# module.net
KiCad netlist of a schematic drawn in EAGLE
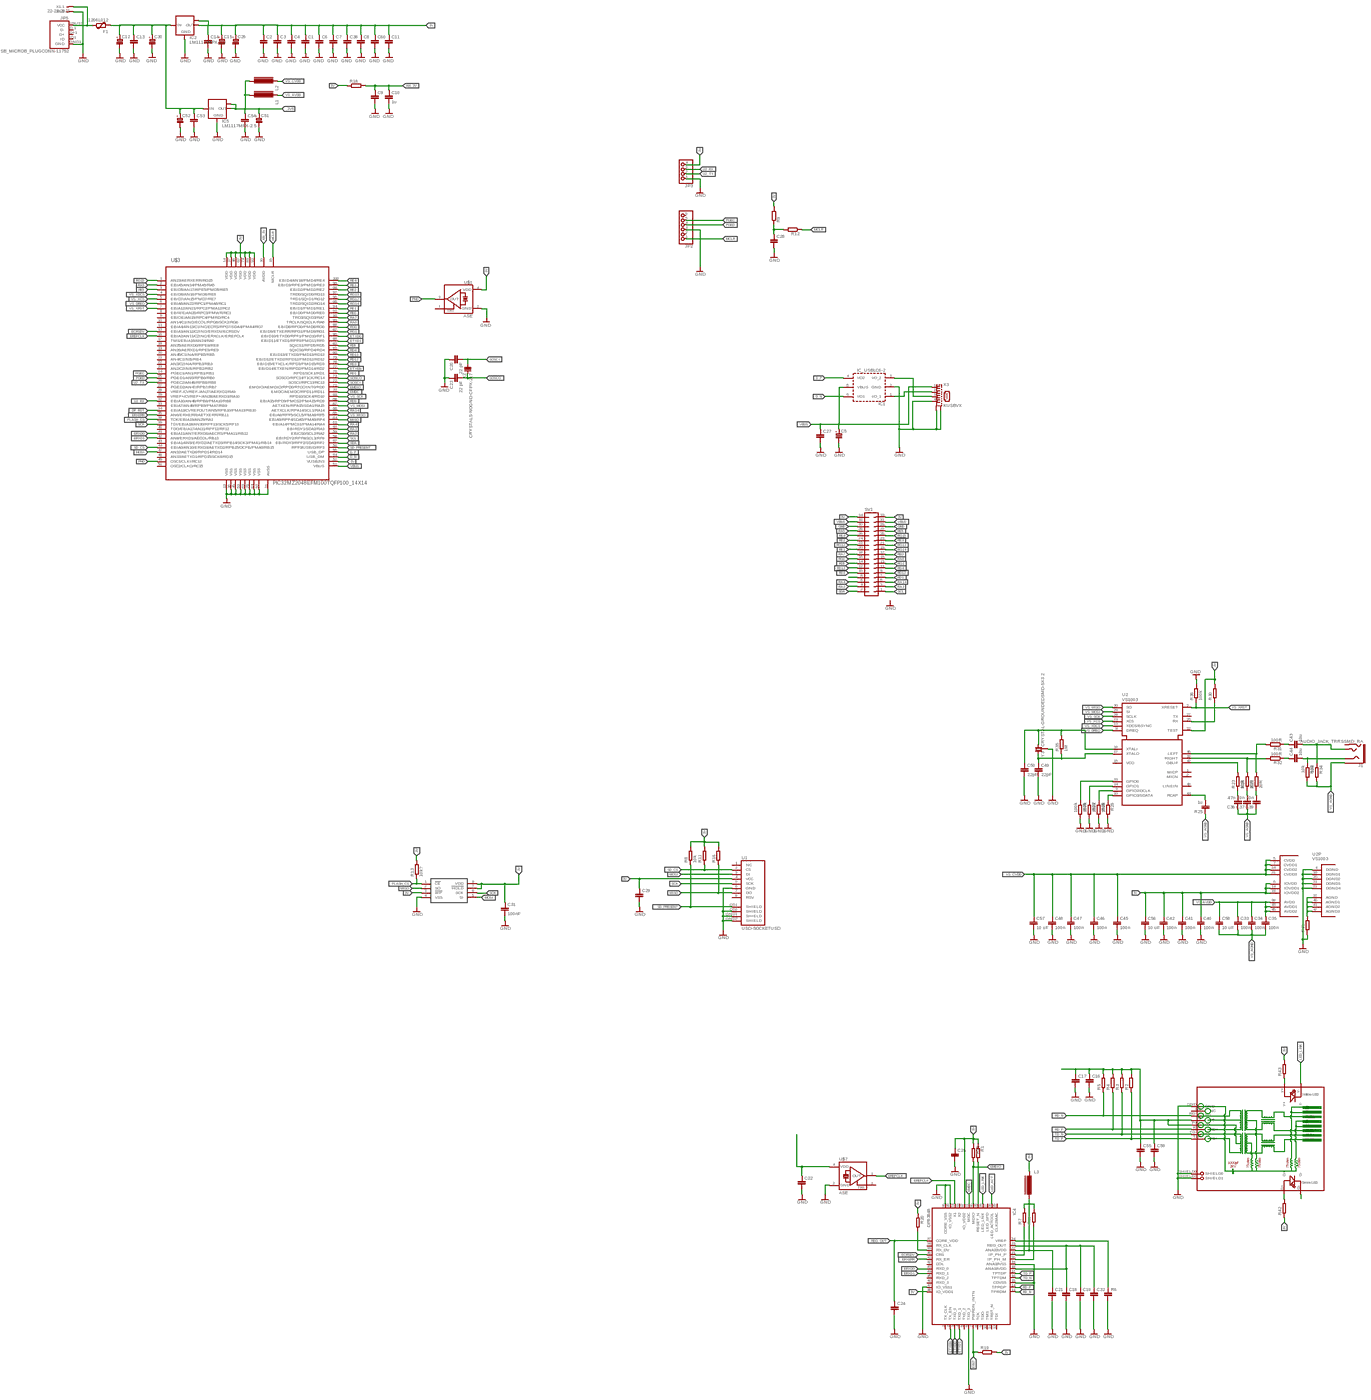
[diagram p0: schematic, sheet 1, overview]
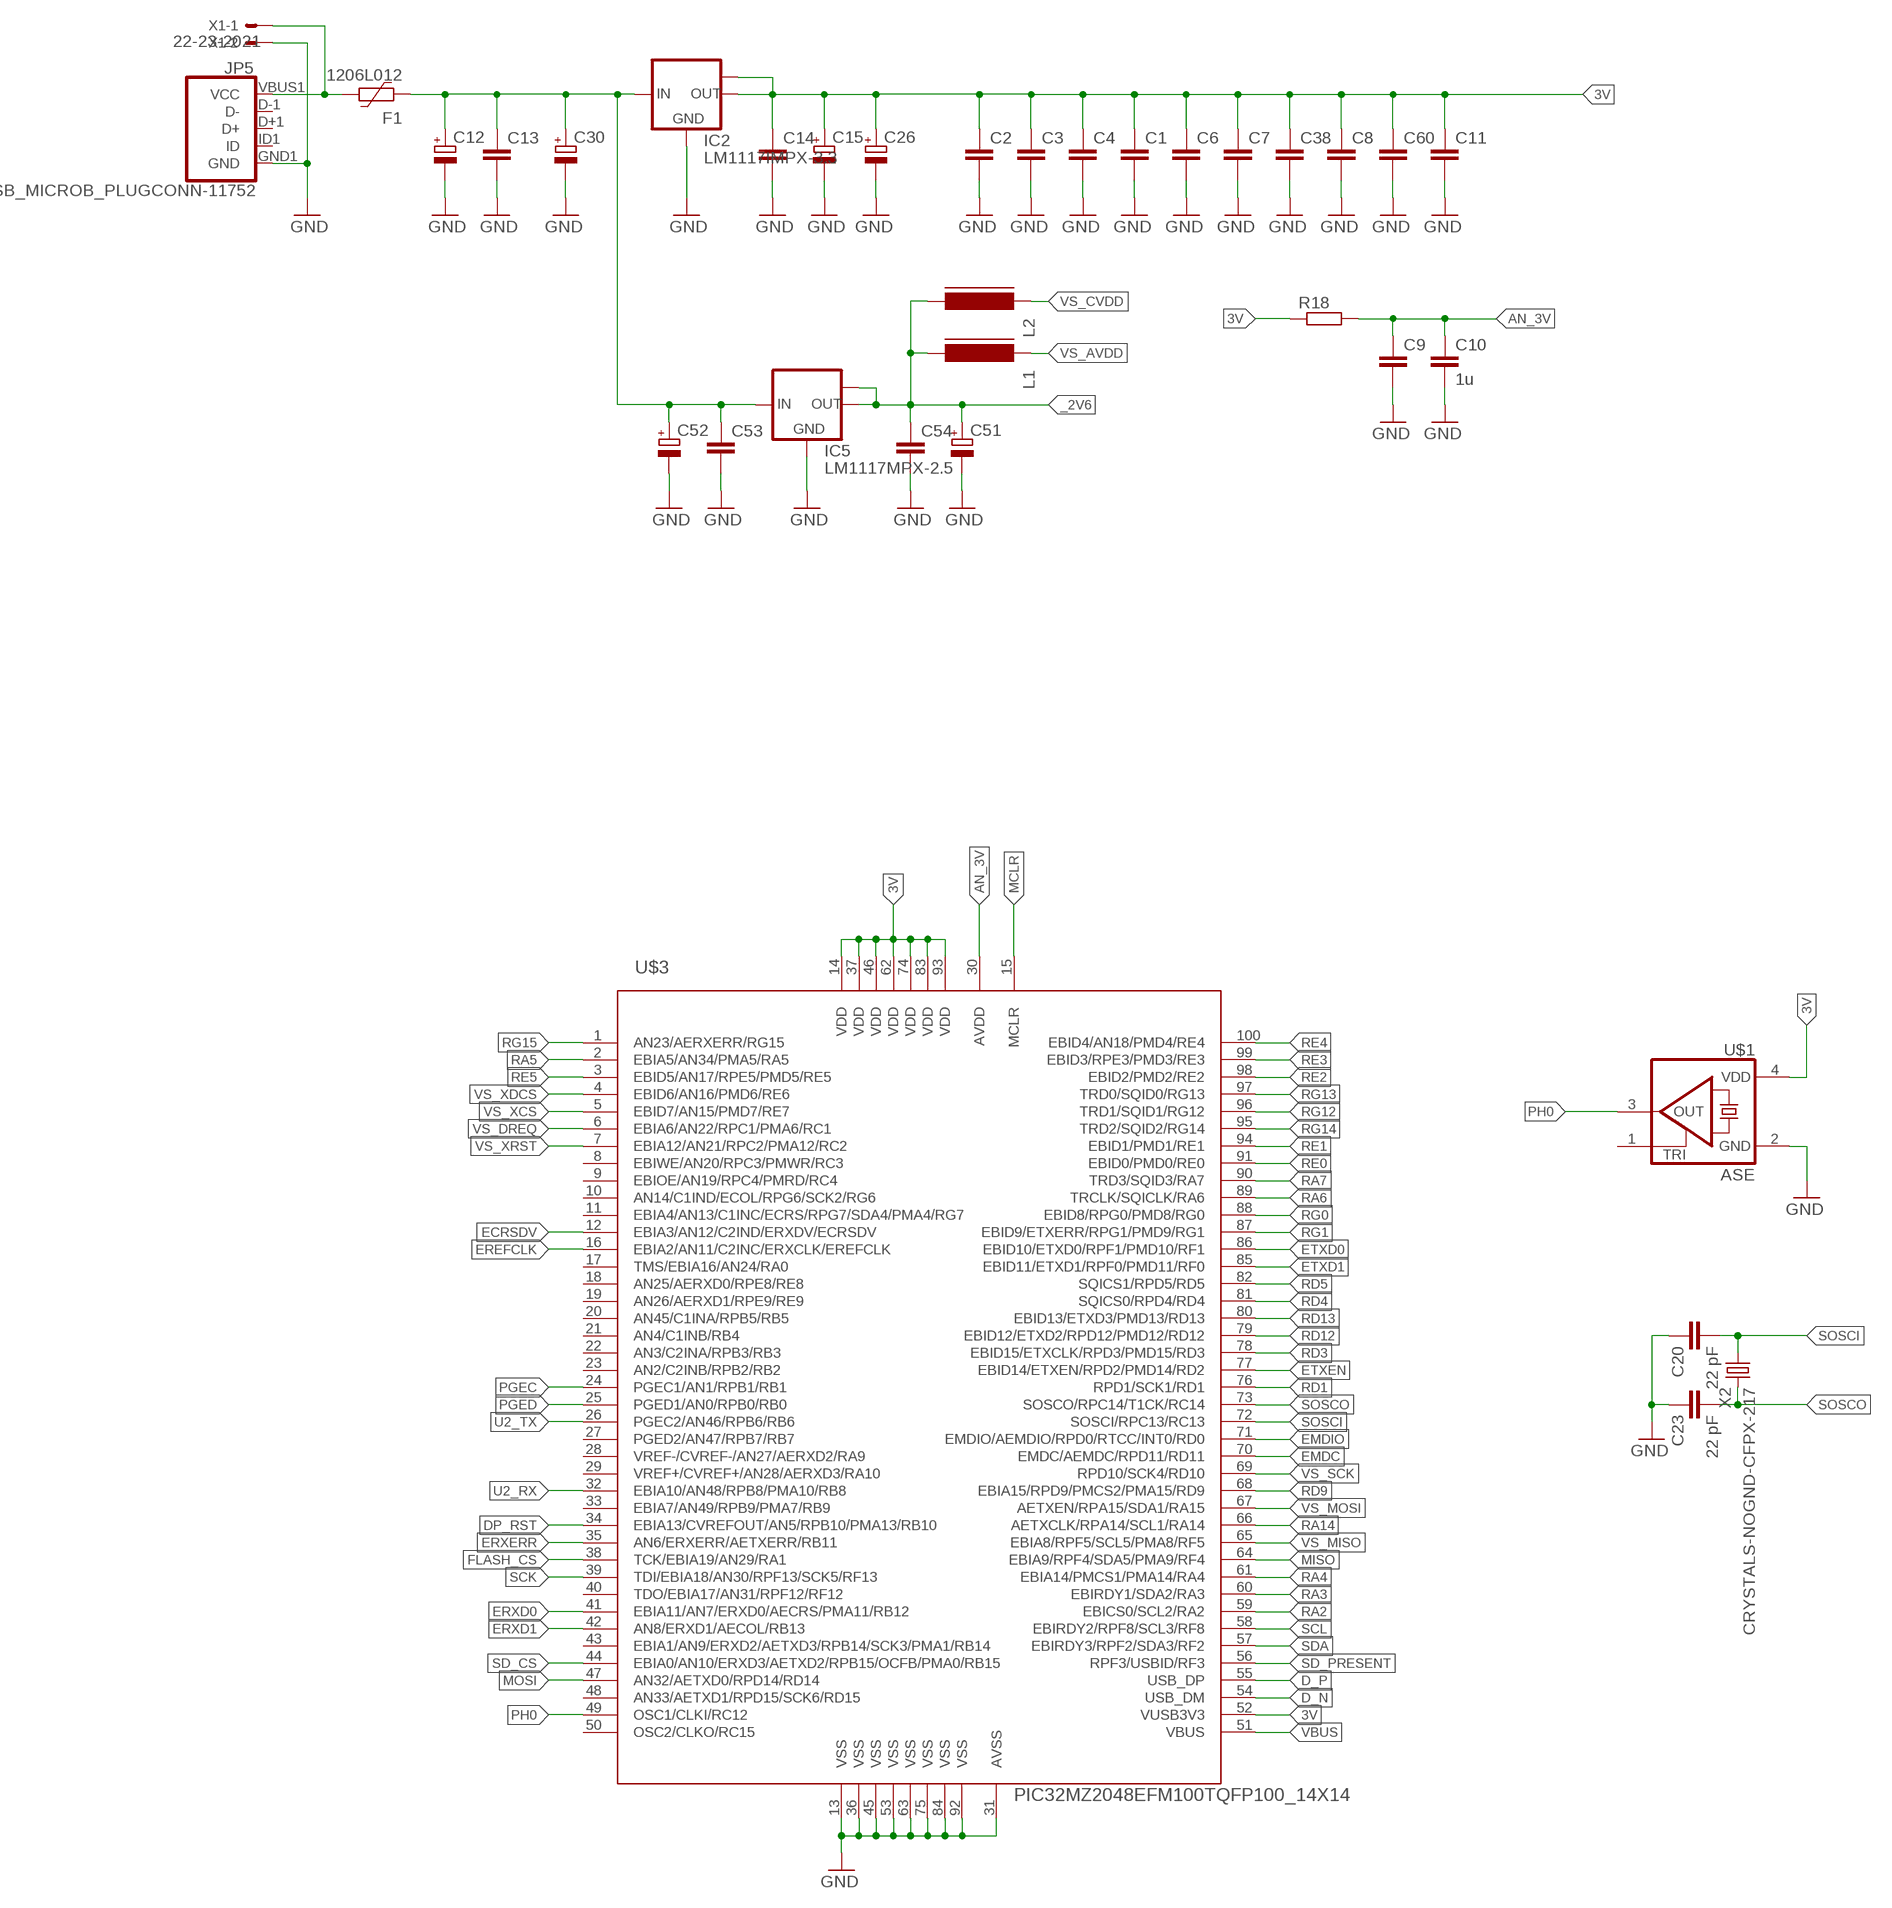
[diagram p1: schematic, sheet 1, part 1 of 4]
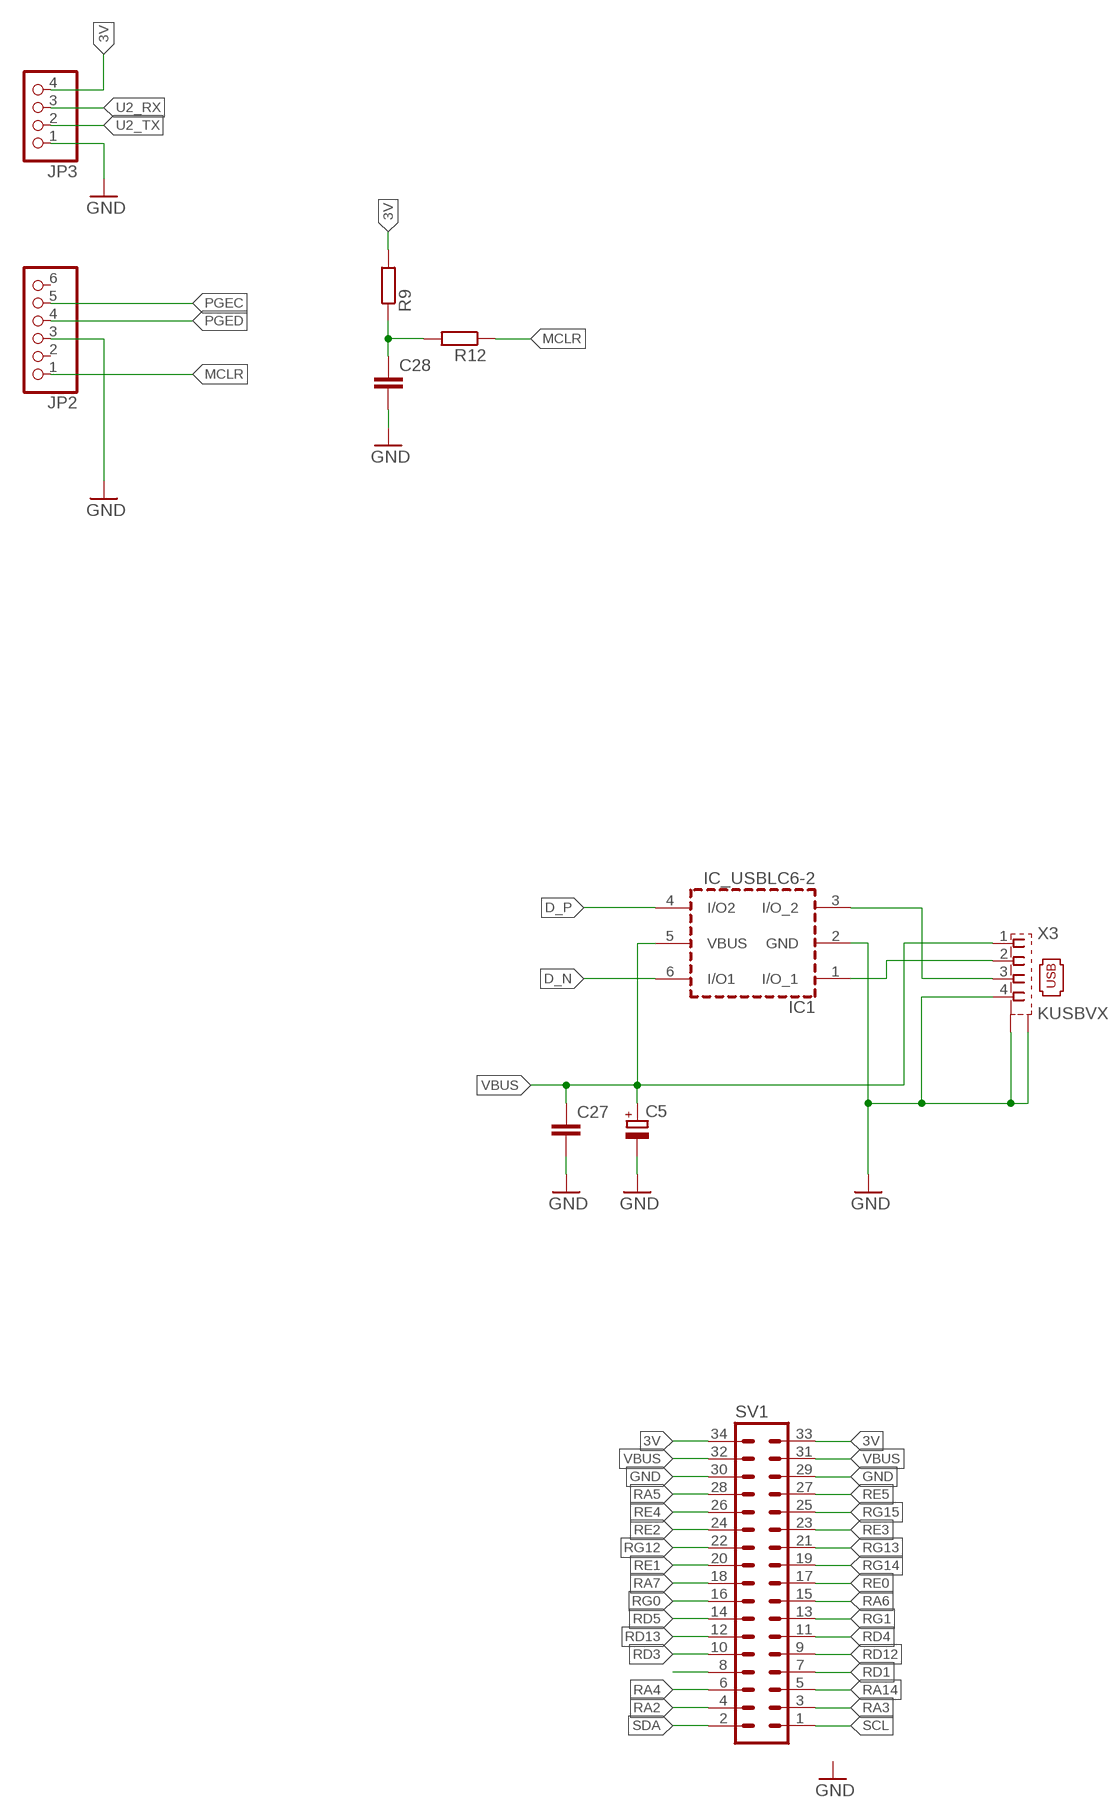
[diagram p2: schematic, sheet 1, part 2 of 4]
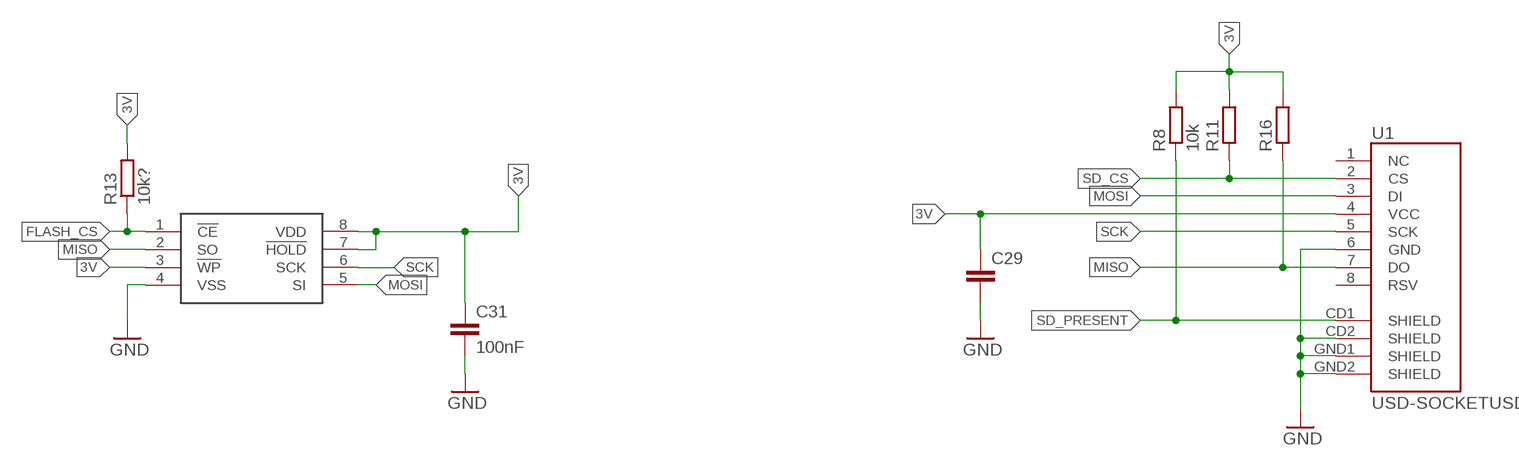
[diagram p3: schematic, sheet 1, part 3 of 4]
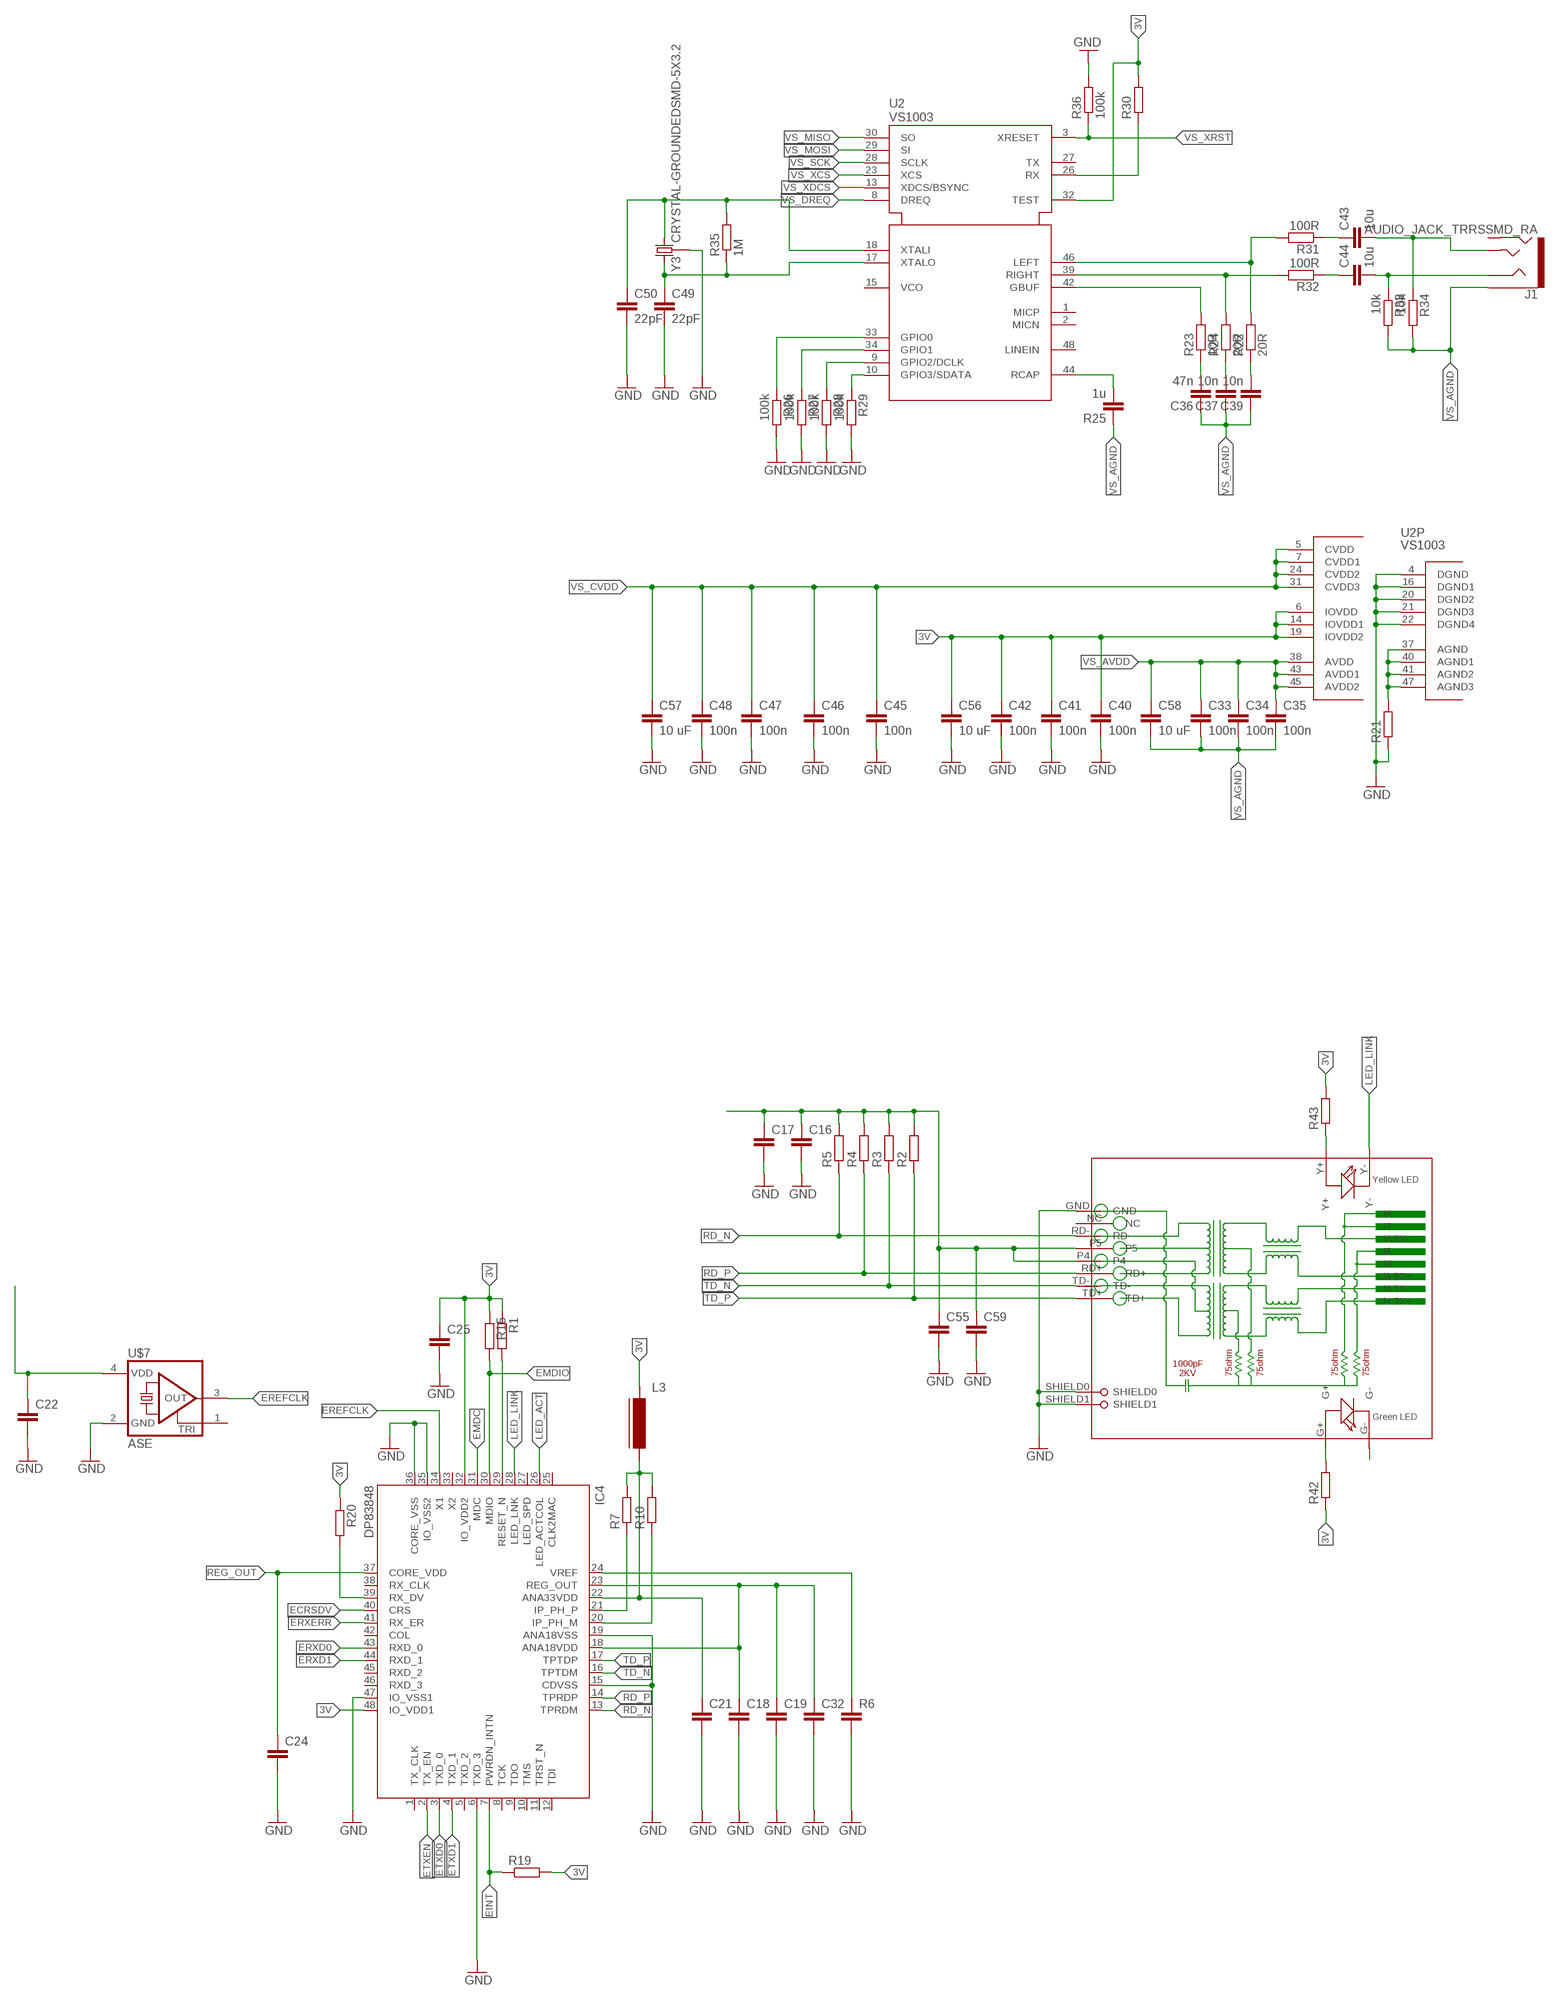
[diagram p4: schematic, sheet 1, part 4 of 4]

(export (version "E")
  (design (tool "Eeschema 10.0.6"))
  (components
    (comp (ref "C1")
      (value "C-EUC0402")
      (footprint "eagle-import:C0402")
      (libsource (lib "eagle-import") (part "C-EUC0402"))
    )
    (comp (ref "C2")
      (value "C-EUC0402")
      (footprint "eagle-import:C0402")
      (libsource (lib "eagle-import") (part "C-EUC0402"))
    )
    (comp (ref "C3")
      (value "C-EUC0402")
      (footprint "eagle-import:C0402")
      (libsource (lib "eagle-import") (part "C-EUC0402"))
    )
    (comp (ref "C4")
      (value "C-EUC0402")
      (footprint "eagle-import:C0402")
      (libsource (lib "eagle-import") (part "C-EUC0402"))
    )
    (comp (ref "C5")
      (value "CPOL-EUSMCA")
      (footprint "eagle-import:SMC_A")
      (libsource (lib "eagle-import") (part "CPOL-EUSMCA"))
    )
    (comp (ref "C6")
      (value "C-EUC0402")
      (footprint "eagle-import:C0402")
      (libsource (lib "eagle-import") (part "C-EUC0402"))
    )
    (comp (ref "C7")
      (value "C-EUC0402")
      (footprint "eagle-import:C0402")
      (libsource (lib "eagle-import") (part "C-EUC0402"))
    )
    (comp (ref "C8")
      (value "C-EUC0402")
      (footprint "eagle-import:C0402")
      (libsource (lib "eagle-import") (part "C-EUC0402"))
    )
    (comp (ref "C9")
      (value "C-EUC0402")
      (footprint "eagle-import:C0402")
      (libsource (lib "eagle-import") (part "C-EUC0402"))
    )
    (comp (ref "C10")
      (value "1u")
      (footprint "eagle-import:C0603")
      (libsource (lib "eagle-import") (part "C-EUC0603"))
    )
    (comp (ref "C11")
      (value "C-EUC0402")
      (footprint "eagle-import:C0402")
      (libsource (lib "eagle-import") (part "C-EUC0402"))
    )
    (comp (ref "C12")
      (value "CPOL-EUSMCB")
      (footprint "eagle-import:SMC_B")
      (libsource (lib "eagle-import") (part "CPOL-EUSMCB"))
    )
    (comp (ref "C13")
      (value "C-EUC0603")
      (footprint "eagle-import:C0603")
      (libsource (lib "eagle-import") (part "C-EUC0603"))
    )
    (comp (ref "C14")
      (value "C-EUC0603")
      (footprint "eagle-import:C0603")
      (libsource (lib "eagle-import") (part "C-EUC0603"))
    )
    (comp (ref "C15")
      (value "CPOL-EUSMCB")
      (footprint "eagle-import:SMC_B")
      (libsource (lib "eagle-import") (part "CPOL-EUSMCB"))
    )
    (comp (ref "C16")
      (value "C-EUC0603")
      (footprint "eagle-import:C0603")
      (libsource (lib "eagle-import") (part "C-EUC0603"))
    )
    (comp (ref "C17")
      (value "C-EUC0603")
      (footprint "eagle-import:C0603")
      (libsource (lib "eagle-import") (part "C-EUC0603"))
    )
    (comp (ref "C18")
      (value "C-EUC0402")
      (footprint "eagle-import:C0402")
      (libsource (lib "eagle-import") (part "C-EUC0402"))
    )
    (comp (ref "C19")
      (value "C-EUC0402")
      (footprint "eagle-import:C0402")
      (libsource (lib "eagle-import") (part "C-EUC0402"))
    )
    (comp (ref "C20")
      (value "22 pF")
      (footprint "eagle-import:C0603")
      (libsource (lib "eagle-import") (part "C-EUC0603"))
    )
    (comp (ref "C21")
      (value "C-EUC0402")
      (footprint "eagle-import:C0402")
      (libsource (lib "eagle-import") (part "C-EUC0402"))
    )
    (comp (ref "C22")
      (value "C-EUC0402")
      (footprint "eagle-import:C0402")
      (libsource (lib "eagle-import") (part "C-EUC0402"))
    )
    (comp (ref "C23")
      (value "22 pF")
      (footprint "eagle-import:C0603")
      (libsource (lib "eagle-import") (part "C-EUC0603"))
    )
    (comp (ref "C24")
      (value "C-EUC0603")
      (footprint "eagle-import:C0603")
      (libsource (lib "eagle-import") (part "C-EUC0603"))
    )
    (comp (ref "C25")
      (value "C-EUC0603")
      (footprint "eagle-import:C0603")
      (libsource (lib "eagle-import") (part "C-EUC0603"))
    )
    (comp (ref "C26")
      (value "CPOL-EUSMCA")
      (footprint "eagle-import:SMC_A")
      (libsource (lib "eagle-import") (part "CPOL-EUSMCA"))
    )
    (comp (ref "C27")
      (value "C-EUC0603")
      (footprint "eagle-import:C0603")
      (libsource (lib "eagle-import") (part "C-EUC0603"))
    )
    (comp (ref "C28")
      (value "C-EUC0603")
      (footprint "eagle-import:C0603")
      (libsource (lib "eagle-import") (part "C-EUC0603"))
    )
    (comp (ref "C29")
      (value "C-EUC0603")
      (footprint "eagle-import:C0603")
      (libsource (lib "eagle-import") (part "C-EUC0603"))
    )
    (comp (ref "C30")
      (value "CPOL-EUSMCA")
      (footprint "eagle-import:SMC_A")
      (libsource (lib "eagle-import") (part "CPOL-EUSMCA"))
    )
    (comp (ref "C31")
      (value "100nF")
      (footprint "eagle-import:C0603")
      (libsource (lib "eagle-import") (part "C-EUC0603"))
    )
    (comp (ref "C32")
      (value "C-EUC0603")
      (footprint "eagle-import:C0603")
      (libsource (lib "eagle-import") (part "C-EUC0603"))
    )
    (comp (ref "C33")
      (value "100n")
      (footprint "eagle-import:C0603")
      (libsource (lib "eagle-import") (part "C-EUC0603"))
    )
    (comp (ref "C34")
      (value "100n")
      (footprint "eagle-import:C0603")
      (libsource (lib "eagle-import") (part "C-EUC0603"))
    )
    (comp (ref "C35")
      (value "100n")
      (footprint "eagle-import:C0603")
      (libsource (lib "eagle-import") (part "C-EUC0603"))
    )
    (comp (ref "C36")
      (value "47n")
      (footprint "eagle-import:C0603")
      (libsource (lib "eagle-import") (part "C-EUC0603"))
    )
    (comp (ref "C37")
      (value "10n")
      (footprint "eagle-import:C0603")
      (libsource (lib "eagle-import") (part "C-EUC0603"))
    )
    (comp (ref "C38")
      (value "C-EUC0402")
      (footprint "eagle-import:C0402")
      (libsource (lib "eagle-import") (part "C-EUC0402"))
    )
    (comp (ref "C39")
      (value "10n")
      (footprint "eagle-import:C0603")
      (libsource (lib "eagle-import") (part "C-EUC0603"))
    )
    (comp (ref "C40")
      (value "100n")
      (footprint "eagle-import:C0402")
      (libsource (lib "eagle-import") (part "C-EUC0402"))
    )
    (comp (ref "C41")
      (value "100n")
      (footprint "eagle-import:C0402")
      (libsource (lib "eagle-import") (part "C-EUC0402"))
    )
    (comp (ref "C42")
      (value "100n")
      (footprint "eagle-import:C0402")
      (libsource (lib "eagle-import") (part "C-EUC0402"))
    )
    (comp (ref "C43")
      (value "10u")
      (footprint "eagle-import:C0603")
      (libsource (lib "eagle-import") (part "C-EUC0603"))
    )
    (comp (ref "C44")
      (value "10u")
      (footprint "eagle-import:C0603")
      (libsource (lib "eagle-import") (part "C-EUC0603"))
    )
    (comp (ref "C45")
      (value "100n")
      (footprint "eagle-import:C0402")
      (libsource (lib "eagle-import") (part "C-EUC0402"))
    )
    (comp (ref "C46")
      (value "100n")
      (footprint "eagle-import:C0603")
      (libsource (lib "eagle-import") (part "C-EUC0603"))
    )
    (comp (ref "C47")
      (value "100n")
      (footprint "eagle-import:C0603")
      (libsource (lib "eagle-import") (part "C-EUC0603"))
    )
    (comp (ref "C48")
      (value "100n")
      (footprint "eagle-import:C0603")
      (libsource (lib "eagle-import") (part "C-EUC0603"))
    )
    (comp (ref "C49")
      (value "22pF")
      (footprint "eagle-import:C0603")
      (libsource (lib "eagle-import") (part "C-EUC0603"))
    )
    (comp (ref "C50")
      (value "22pF")
      (footprint "eagle-import:C0603")
      (libsource (lib "eagle-import") (part "C-EUC0603"))
    )
    (comp (ref "C51")
      (value "CPOL-EUSMCB")
      (footprint "eagle-import:SMC_B")
      (libsource (lib "eagle-import") (part "CPOL-EUSMCB"))
    )
    (comp (ref "C52")
      (value "CPOL-EUSMCB")
      (footprint "eagle-import:SMC_B")
      (libsource (lib "eagle-import") (part "CPOL-EUSMCB"))
    )
    (comp (ref "C53")
      (value "C-EUC1206")
      (footprint "eagle-import:C1206")
      (libsource (lib "eagle-import") (part "C-EUC1206"))
    )
    (comp (ref "C54")
      (value "C-EUC1206")
      (footprint "eagle-import:C1206")
      (libsource (lib "eagle-import") (part "C-EUC1206"))
    )
    (comp (ref "C55")
      (value "C-EUC0603")
      (footprint "eagle-import:C0603")
      (libsource (lib "eagle-import") (part "C-EUC0603"))
    )
    (comp (ref "C56")
      (value "10 uF")
      (footprint "eagle-import:C0603")
      (libsource (lib "eagle-import") (part "C-EUC0603"))
    )
    (comp (ref "C57")
      (value "10 uF")
      (footprint "eagle-import:C0603")
      (libsource (lib "eagle-import") (part "C-EUC0603"))
    )
    (comp (ref "C58")
      (value "10 uF")
      (footprint "eagle-import:C0603")
      (libsource (lib "eagle-import") (part "C-EUC0603"))
    )
    (comp (ref "C59")
      (value "C-EUC0603")
      (footprint "eagle-import:C0603")
      (libsource (lib "eagle-import") (part "C-EUC0603"))
    )
    (comp (ref "C60")
      (value "C-EUC0402")
      (footprint "eagle-import:C0402")
      (libsource (lib "eagle-import") (part "C-EUC0402"))
    )
    (comp (ref "F1")
      (value "1206L012")
      (footprint "eagle-import:1206L")
      (fields (field (name "MF") "Littelfuse"))
      (libsource (lib "eagle-import") (part "?1206L012"))
    )
    (comp (ref "IC1")
      (value "IC_USBLC6-2")
      (footprint "eagle-import:SOT-23-6L")
      (libsource (lib "eagle-import") (part "IC_USBLC6-2"))
    )
    (comp (ref "IC2")
      (value "LM1117IMPX-3.3")
      (footprint "eagle-import:SOT223")
      (libsource (lib "eagle-import") (part "LM1117IMPX-3.3"))
    )
    (comp (ref "IC4")
      (value "DP83848")
      (footprint "eagle-import:LQFP48")
      (fields (field (name "MPN") "DP83848VYB"))
      (libsource (lib "eagle-import") (part "DP83848"))
    )
    (comp (ref "IC5")
      (value "LM1117MPX-2.5")
      (footprint "eagle-import:SOT223")
      (libsource (lib "eagle-import") (part "LM1117MPX-2.5"))
    )
    (comp (ref "J1")
      (value "AUDIO_JACK_TRRSSMD_RA")
      (footprint "eagle-import:AUDIO_JACK_3.5MM_TRRS_SMD_RA")
      (libsource (lib "eagle-import") (part "AUDIO_JACK_TRRSSMD_RA"))
    )
    (comp (ref "JP2")
      (value "PINHD-1X6")
      (footprint "eagle-import:1X06")
      (libsource (lib "eagle-import") (part "PINHD-1X6"))
    )
    (comp (ref "JP3")
      (value "PINHD-1X4")
      (footprint "eagle-import:1X04")
      (libsource (lib "eagle-import") (part "PINHD-1X4"))
    )
    (comp (ref "JP5")
      (value "USB_MICROB_PLUGCONN-11752")
      (footprint "eagle-import:USB-B-MICRO-SMD_V03")
      (libsource (lib "eagle-import") (part "USB_MICROB_PLUGCONN-11752"))
    )
    (comp (ref "L1")
      (value "FERRITE-0805")
      (footprint "eagle-import:FB805")
      (libsource (lib "eagle-import") (part "FERRITE-0805"))
    )
    (comp (ref "L2")
      (value "FERRITE-0805")
      (footprint "eagle-import:FB805")
      (libsource (lib "eagle-import") (part "FERRITE-0805"))
    )
    (comp (ref "L3")
      (value "FERRITE-0805")
      (footprint "eagle-import:FB805")
      (libsource (lib "eagle-import") (part "FERRITE-0805"))
    )
    (comp (ref "R1")
      (value "R-EU_R0402")
      (footprint "eagle-import:R0402")
      (libsource (lib "eagle-import") (part "R-EU_R0402"))
    )
    (comp (ref "R2")
      (value "R-EU_R0603")
      (footprint "eagle-import:R0603")
      (libsource (lib "eagle-import") (part "R-EU_R0603"))
    )
    (comp (ref "R3")
      (value "R-EU_R0603")
      (footprint "eagle-import:R0603")
      (libsource (lib "eagle-import") (part "R-EU_R0603"))
    )
    (comp (ref "R4")
      (value "R-EU_R0603")
      (footprint "eagle-import:R0603")
      (libsource (lib "eagle-import") (part "R-EU_R0603"))
    )
    (comp (ref "R5")
      (value "R-EU_R0603")
      (footprint "eagle-import:R0603")
      (libsource (lib "eagle-import") (part "R-EU_R0603"))
    )
    (comp (ref "R6")
      (value "C-EUC0603")
      (footprint "eagle-import:C0603")
      (libsource (lib "eagle-import") (part "C-EUC0603"))
    )
    (comp (ref "R7")
      (value "R-EU_R0402")
      (footprint "eagle-import:R0402")
      (libsource (lib "eagle-import") (part "R-EU_R0402"))
    )
    (comp (ref "R8")
      (value "10k")
      (footprint "eagle-import:R0603")
      (libsource (lib "eagle-import") (part "R-EU_R0603"))
    )
    (comp (ref "R9")
      (value "R-EU_R0603")
      (footprint "eagle-import:R0603")
      (libsource (lib "eagle-import") (part "R-EU_R0603"))
    )
    (comp (ref "R10")
      (value "R-EU_R0402")
      (footprint "eagle-import:R0402")
      (libsource (lib "eagle-import") (part "R-EU_R0402"))
    )
    (comp (ref "R11")
      (value "R-EU_R0603")
      (footprint "eagle-import:R0603")
      (libsource (lib "eagle-import") (part "R-EU_R0603"))
    )
    (comp (ref "R12")
      (value "R-EU_R0402")
      (footprint "eagle-import:R0402")
      (libsource (lib "eagle-import") (part "R-EU_R0402"))
    )
    (comp (ref "R13")
      (value "10k?")
      (footprint "eagle-import:R0603")
      (libsource (lib "eagle-import") (part "R-EU_R0603"))
    )
    (comp (ref "R15")
      (value "R-EU_R0603")
      (footprint "eagle-import:R0603")
      (libsource (lib "eagle-import") (part "R-EU_R0603"))
    )
    (comp (ref "R16")
      (value "R-EU_R0603")
      (footprint "eagle-import:R0603")
      (libsource (lib "eagle-import") (part "R-EU_R0603"))
    )
    (comp (ref "R18")
      (value "R-EU_R0805")
      (footprint "eagle-import:R0805")
      (libsource (lib "eagle-import") (part "R-EU_R0805"))
    )
    (comp (ref "R19")
      (value "R-EU_R0402")
      (footprint "eagle-import:R0402")
      (libsource (lib "eagle-import") (part "R-EU_R0402"))
    )
    (comp (ref "R20")
      (value "R-EU_R0603")
      (footprint "eagle-import:R0603")
      (libsource (lib "eagle-import") (part "R-EU_R0603"))
    )
    (comp (ref "R21")
      (value "R-EU_R0603")
      (footprint "eagle-import:R0603")
      (libsource (lib "eagle-import") (part "R-EU_R0603"))
    )
    (comp (ref "R22")
      (value "20R")
      (footprint "eagle-import:R0603")
      (libsource (lib "eagle-import") (part "R-EU_R0603"))
    )
    (comp (ref "R23")
      (value "10R")
      (footprint "eagle-import:R0603")
      (libsource (lib "eagle-import") (part "R-EU_R0603"))
    )
    (comp (ref "R24")
      (value "20R")
      (footprint "eagle-import:R0603")
      (libsource (lib "eagle-import") (part "R-EU_R0603"))
    )
    (comp (ref "R25")
      (value "1u")
      (footprint "eagle-import:C0603")
      (libsource (lib "eagle-import") (part "C-EUC0603"))
    )
    (comp (ref "R26")
      (value "100k")
      (footprint "eagle-import:R0402")
      (libsource (lib "eagle-import") (part "R-EU_R0402"))
    )
    (comp (ref "R27")
      (value "100k")
      (footprint "eagle-import:R0402")
      (libsource (lib "eagle-import") (part "R-EU_R0402"))
    )
    (comp (ref "R28")
      (value "100k")
      (footprint "eagle-import:R0402")
      (libsource (lib "eagle-import") (part "R-EU_R0402"))
    )
    (comp (ref "R29")
      (value "100k")
      (footprint "eagle-import:R0402")
      (libsource (lib "eagle-import") (part "R-EU_R0402"))
    )
    (comp (ref "R30")
      (value "R-EU_0204/7")
      (footprint "eagle-import:0204_7")
      (libsource (lib "eagle-import") (part "R-EU_0204/7"))
    )
    (comp (ref "R31")
      (value "100R")
      (footprint "eagle-import:R0603")
      (libsource (lib "eagle-import") (part "R-EU_R0603"))
    )
    (comp (ref "R32")
      (value "100R")
      (footprint "eagle-import:R0603")
      (libsource (lib "eagle-import") (part "R-EU_R0603"))
    )
    (comp (ref "R33")
      (value "10k")
      (footprint "eagle-import:R0603")
      (libsource (lib "eagle-import") (part "R-EU_R0603"))
    )
    (comp (ref "R34")
      (value "10k")
      (footprint "eagle-import:R0603")
      (libsource (lib "eagle-import") (part "R-EU_R0603"))
    )
    (comp (ref "R35")
      (value "1M")
      (footprint "eagle-import:R0603")
      (libsource (lib "eagle-import") (part "R-EU_R0603"))
    )
    (comp (ref "R36")
      (value "100k")
      (footprint "eagle-import:R0603")
      (libsource (lib "eagle-import") (part "R-EU_R0603"))
    )
    (comp (ref "R42")
      (value "R-EU_R0603")
      (footprint "eagle-import:R0603")
      (libsource (lib "eagle-import") (part "R-EU_R0603"))
    )
    (comp (ref "R43")
      (value "R-EU_R0603")
      (footprint "eagle-import:R0603")
      (libsource (lib "eagle-import") (part "R-EU_R0603"))
    )
    (comp (ref "RJ1")
      (value "HR911105A")
      (footprint "eagle-import:HR911105A")
      (libsource (lib "eagle-import") (part "HR911105A"))
    )
    (comp (ref "SV1")
      (value "ML34L")
      (footprint "eagle-import:ML34L")
      (libsource (lib "eagle-import") (part "ML34L"))
    )
    (comp (ref "U$1")
      (value "ASE")
      (footprint "eagle-import:ASE")
      (libsource (lib "eagle-import") (part "ASE"))
    )
    (comp (ref "U$2")
      (value "SST25VF016BSO8M")
      (footprint "eagle-import:SO-08M")
      (libsource (lib "eagle-import") (part "SST25VF016BSO8M"))
    )
    (comp (ref "U$3")
      (value "PIC32MZ2048EFM100TQFP100_14X14")
      (footprint "eagle-import:TQFP100_14X14")
      (libsource (lib "eagle-import") (part "PIC32MZ2048EFM100TQFP100_14X14"))
    )
    (comp (ref "U$7")
      (value "ASE")
      (footprint "eagle-import:ASE")
      (libsource (lib "eagle-import") (part "ASE"))
    )
    (comp (ref "U1")
      (value "USD-SOCKETUSD")
      (footprint "eagle-import:USD-SOCKET-PP")
      (libsource (lib "eagle-import") (part "USD-SOCKETUSD"))
    )
    (comp (ref "U2")
      (value "VS1003")
      (footprint "eagle-import:LQFP48")
      (libsource (lib "eagle-import") (part "VS1003"))
    )
    (comp (ref "X1")
      (value "22-23-2021")
      (footprint "eagle-import:22-23-2021")
      (fields (field (name "MF") "MOLEX"))
      (libsource (lib "eagle-import") (part "22-23-2021"))
    )
    (comp (ref "X2")
      (value "CRYSTALS-NOGND-CFPX-217")
      (footprint "eagle-import:3.2X1.5-2-PAD")
      (libsource (lib "eagle-import") (part "CRYSTALS-NOGND-CFPX-217"))
    )
    (comp (ref "X3")
      (value "KUSBVX")
      (footprint "eagle-import:KUSBVX")
      (libsource (lib "eagle-import") (part "KUSBVX"))
    )
    (comp (ref "Y3")
      (value "CRYSTAL-GROUNDEDSMD-5X3.2")
      (footprint "eagle-import:CRYSTAL-SMD-5X3.2-4PAD")
      (libsource (lib "eagle-import") (part "CRYSTAL-GROUNDEDSMD-5X3.2"))
    )
  )
  (nets
    (net (code "1") (name "/A3V") (class "Default")
      (node (ref "C16") (pin "1") (pinfunction "1_1") (pintype "passive"))
      (node (ref "C17") (pin "1") (pinfunction "1_1") (pintype "passive"))
      (node (ref "C21") (pin "1") (pinfunction "1_1") (pintype "passive"))
      (node (ref "C55") (pin "1") (pinfunction "1_1") (pintype "passive"))
      (node (ref "C59") (pin "1") (pinfunction "1_1") (pintype "passive"))
      (node (ref "IC4") (pin "22") (pinfunction "ANA33VDD_22") (pintype "power_in"))
      (node (ref "L3") (pin "2") (pinfunction "2_2") (pintype "passive"))
      (node (ref "R10") (pin "2") (pinfunction "2_2") (pintype "passive"))
      (node (ref "R2") (pin "2") (pinfunction "2_2") (pintype "passive"))
      (node (ref "R3") (pin "2") (pinfunction "2_2") (pintype "passive"))
      (node (ref "R4") (pin "2") (pinfunction "2_2") (pintype "passive"))
      (node (ref "R5") (pin "2") (pinfunction "2_2") (pintype "passive"))
      (node (ref "R7") (pin "2") (pinfunction "2_2") (pintype "passive"))
      (node (ref "RJ1") (pin "P4") (pinfunction "P4_P4") (pintype "bidirectional"))
      (node (ref "RJ1") (pin "P5") (pinfunction "P5_P5") (pintype "bidirectional"))
    )
    (net (code "2") (name "3V") (class "Default")
      (node (ref "C1") (pin "1") (pinfunction "1_1") (pintype "passive"))
      (node (ref "C11") (pin "1") (pinfunction "1_1") (pintype "passive"))
      (node (ref "C14") (pin "1") (pinfunction "1_1") (pintype "passive"))
      (node (ref "C15") (pin "+") (pinfunction "+_+") (pintype "passive"))
      (node (ref "C2") (pin "1") (pinfunction "1_1") (pintype "passive"))
      (node (ref "C22") (pin "1") (pinfunction "1_1") (pintype "passive"))
      (node (ref "C25") (pin "1") (pinfunction "1_1") (pintype "passive"))
      (node (ref "C26") (pin "+") (pinfunction "+_+") (pintype "passive"))
      (node (ref "C29") (pin "1") (pinfunction "1_1") (pintype "passive"))
      (node (ref "C3") (pin "1") (pinfunction "1_1") (pintype "passive"))
      (node (ref "C31") (pin "1") (pinfunction "1_1") (pintype "passive"))
      (node (ref "C38") (pin "1") (pinfunction "1_1") (pintype "passive"))
      (node (ref "C4") (pin "1") (pinfunction "1_1") (pintype "passive"))
      (node (ref "C40") (pin "1") (pinfunction "1_1") (pintype "passive"))
      (node (ref "C41") (pin "1") (pinfunction "1_1") (pintype "passive"))
      (node (ref "C42") (pin "1") (pinfunction "1_1") (pintype "passive"))
      (node (ref "C56") (pin "1") (pinfunction "1_1") (pintype "passive"))
      (node (ref "C6") (pin "1") (pinfunction "1_1") (pintype "passive"))
      (node (ref "C60") (pin "1") (pinfunction "1_1") (pintype "passive"))
      (node (ref "C7") (pin "1") (pinfunction "1_1") (pintype "passive"))
      (node (ref "C8") (pin "1") (pinfunction "1_1") (pintype "passive"))
      (node (ref "IC2") (pin "2") (pinfunction "OUT_2") (pintype "passive"))
      (node (ref "IC2") (pin "TAB") (pinfunction "OUT1_TAB") (pintype "passive"))
      (node (ref "IC4") (pin "32") (pinfunction "IO_VDD2_32") (pintype "power_in"))
      (node (ref "IC4") (pin "48") (pinfunction "IO_VDD1_48") (pintype "power_in"))
      (node (ref "JP3") (pin "4") (pinfunction "4_4") (pintype "passive"))
      (node (ref "L3") (pin "1") (pinfunction "1_1") (pintype "passive"))
      (node (ref "R1") (pin "1") (pinfunction "1_1") (pintype "passive"))
      (node (ref "R11") (pin "2") (pinfunction "2_2") (pintype "passive"))
      (node (ref "R13") (pin "2") (pinfunction "2_2") (pintype "passive"))
      (node (ref "R15") (pin "1") (pinfunction "1_1") (pintype "passive"))
      (node (ref "R16") (pin "2") (pinfunction "2_2") (pintype "passive"))
      (node (ref "R18") (pin "1") (pinfunction "1_1") (pintype "passive"))
      (node (ref "R19") (pin "2") (pinfunction "2_2") (pintype "passive"))
      (node (ref "R20") (pin "1") (pinfunction "1_1") (pintype "passive"))
      (node (ref "R30") (pin "2") (pinfunction "2_2") (pintype "passive"))
      (node (ref "R42") (pin "1") (pinfunction "1_1") (pintype "passive"))
      (node (ref "R43") (pin "2") (pinfunction "2_2") (pintype "passive"))
      (node (ref "R8") (pin "2") (pinfunction "2_2") (pintype "passive"))
      (node (ref "R9") (pin "2") (pinfunction "2_2") (pintype "passive"))
      (node (ref "SV1") (pin "33") (pinfunction "33_33") (pintype "passive"))
      (node (ref "SV1") (pin "34") (pinfunction "34_34") (pintype "passive"))
      (node (ref "U$1") (pin "4") (pinfunction "VDD_4") (pintype "power_in"))
      (node (ref "U$2") (pin "3") (pinfunction "~{WP}_3") (pintype "bidirectional"))
      (node (ref "U$2") (pin "7") (pinfunction "~{HOLD}_7") (pintype "bidirectional"))
      (node (ref "U$2") (pin "8") (pinfunction "VDD_8") (pintype "bidirectional"))
      (node (ref "U$3") (pin "14") (pinfunction "VDD_14") (pintype "bidirectional"))
      (node (ref "U$3") (pin "37") (pinfunction "VDD_37") (pintype "bidirectional"))
      (node (ref "U$3") (pin "46") (pinfunction "VDD_46") (pintype "bidirectional"))
      (node (ref "U$3") (pin "52") (pinfunction "VUSB3V3_52") (pintype "bidirectional"))
      (node (ref "U$3") (pin "62") (pinfunction "VDD_62") (pintype "bidirectional"))
      (node (ref "U$3") (pin "74") (pinfunction "VDD_74") (pintype "bidirectional"))
      (node (ref "U$3") (pin "83") (pinfunction "VDD_83") (pintype "bidirectional"))
      (node (ref "U$3") (pin "93") (pinfunction "VDD_93") (pintype "bidirectional"))
      (node (ref "U$7") (pin "4") (pinfunction "VDD_4") (pintype "power_in"))
      (node (ref "U1") (pin "4") (pinfunction "VCC_4") (pintype "bidirectional"))
      (node (ref "U2") (pin "14") (pinfunction "IOVDD1_14") (pintype "power_in"))
      (node (ref "U2") (pin "19") (pinfunction "IOVDD2_19") (pintype "power_in"))
      (node (ref "U2") (pin "32") (pinfunction "TEST_32") (pintype "bidirectional"))
      (node (ref "U2") (pin "6") (pinfunction "IOVDD_6") (pintype "power_in"))
    )
    (net (code "3") (name "AN_3V") (class "Default")
      (node (ref "C10") (pin "1") (pinfunction "1_1") (pintype "passive"))
      (node (ref "C9") (pin "1") (pinfunction "1_1") (pintype "passive"))
      (node (ref "R18") (pin "2") (pinfunction "2_2") (pintype "passive"))
      (node (ref "U$3") (pin "30") (pinfunction "AVDD_30") (pintype "bidirectional"))
    )
    (net (code "4") (name "DP_RST") (class "Default")
      (node (ref "IC4") (pin "29") (pinfunction "RESET_N_29") (pintype "input"))
      (node (ref "R1") (pin "2") (pinfunction "2_2") (pintype "passive"))
      (node (ref "U$3") (pin "34") (pinfunction "EBIA13/CVREFOUT/AN5/RPB10/PMA13/RB10_34") (pintype "bidirectional"))
    )
    (net (code "5") (name "D_N") (class "Default")
      (node (ref "IC1") (pin "6") (pinfunction "I/O1_6") (pintype "bidirectional"))
      (node (ref "U$3") (pin "54") (pinfunction "USB_DM_54") (pintype "bidirectional"))
    )
    (net (code "6") (name "D_P") (class "Default")
      (node (ref "IC1") (pin "4") (pinfunction "I/O2_4") (pintype "bidirectional"))
      (node (ref "U$3") (pin "55") (pinfunction "USB_DP_55") (pintype "bidirectional"))
    )
    (net (code "7") (name "ECRSDV") (class "Default")
      (node (ref "IC4") (pin "40") (pinfunction "CRS_40") (pintype "bidirectional"))
      (node (ref "U$3") (pin "12") (pinfunction "EBIA3/AN12/C2IND/ERXDV/ECRSDV_12") (pintype "bidirectional"))
    )
    (net (code "8") (name "EINT") (class "Default")
      (node (ref "IC4") (pin "7") (pinfunction "PWRDN_INTN_7") (pintype "bidirectional"))
      (node (ref "R19") (pin "1") (pinfunction "1_1") (pintype "passive"))
    )
    (net (code "9") (name "EMDC") (class "Default")
      (node (ref "IC4") (pin "31") (pinfunction "MDC_31") (pintype "input"))
      (node (ref "U$3") (pin "70") (pinfunction "EMDC/AEMDC/RPD11/RD11_70") (pintype "bidirectional"))
    )
    (net (code "10") (name "EMDIO") (class "Default")
      (node (ref "IC4") (pin "30") (pinfunction "MDIO_30") (pintype "bidirectional"))
      (node (ref "R15") (pin "2") (pinfunction "2_2") (pintype "passive"))
      (node (ref "U$3") (pin "71") (pinfunction "EMDIO/AEMDIO/RPD0/RTCC/INT0/RD0_71") (pintype "bidirectional"))
    )
    (net (code "11") (name "EREFCLK") (class "Default")
      (node (ref "IC4") (pin "34") (pinfunction "X1_34") (pintype "input"))
      (node (ref "U$3") (pin "16") (pinfunction "EBIA2/AN11/C2INC/ERXCLK/EREFCLK_16") (pintype "bidirectional"))
      (node (ref "U$7") (pin "3") (pinfunction "OUT_3") (pintype "output"))
    )
    (net (code "12") (name "ERXD0") (class "Default")
      (node (ref "IC4") (pin "43") (pinfunction "RXD_0_43") (pintype "bidirectional"))
      (node (ref "U$3") (pin "41") (pinfunction "EBIA11/AN7/ERXD0/AECRS/PMA11/RB12_41") (pintype "bidirectional"))
    )
    (net (code "13") (name "ERXD1") (class "Default")
      (node (ref "IC4") (pin "44") (pinfunction "RXD_1_44") (pintype "bidirectional"))
      (node (ref "U$3") (pin "42") (pinfunction "AN8/ERXD1/AECOL/RB13_42") (pintype "bidirectional"))
    )
    (net (code "14") (name "ERXERR") (class "Default")
      (node (ref "IC4") (pin "41") (pinfunction "RX_ER_41") (pintype "bidirectional"))
      (node (ref "U$3") (pin "35") (pinfunction "AN6/ERXERR/AETXERR/RB11_35") (pintype "bidirectional"))
    )
    (net (code "15") (name "ETXD0") (class "Default")
      (node (ref "IC4") (pin "3") (pinfunction "TXD_0_3") (pintype "bidirectional"))
      (node (ref "U$3") (pin "86") (pinfunction "EBID10/ETXD0/RPF1/PMD10/RF1_86") (pintype "bidirectional"))
    )
    (net (code "16") (name "ETXD1") (class "Default")
      (node (ref "IC4") (pin "4") (pinfunction "TXD_1_4") (pintype "bidirectional"))
      (node (ref "U$3") (pin "85") (pinfunction "EBID11/ETXD1/RPF0/PMD11/RF0_85") (pintype "bidirectional"))
    )
    (net (code "17") (name "ETXEN") (class "Default")
      (node (ref "IC4") (pin "2") (pinfunction "TX_EN_2") (pintype "bidirectional"))
      (node (ref "U$3") (pin "77") (pinfunction "EBID14/ETXEN/RPD2/PMD14/RD2_77") (pintype "bidirectional"))
    )
    (net (code "18") (name "FLASH_CS") (class "Default")
      (node (ref "R13") (pin "1") (pinfunction "1_1") (pintype "passive"))
      (node (ref "U$2") (pin "1") (pinfunction "~{CE}_1") (pintype "bidirectional"))
      (node (ref "U$3") (pin "38") (pinfunction "TCK/EBIA19/AN29/RA1_38") (pintype "bidirectional"))
    )
    (net (code "19") (name "GND") (class "Default")
      (node (ref "C1") (pin "2") (pinfunction "2_2") (pintype "passive"))
      (node (ref "C10") (pin "2") (pinfunction "2_2") (pintype "passive"))
      (node (ref "C11") (pin "2") (pinfunction "2_2") (pintype "passive"))
      (node (ref "C12") (pin "-") (pinfunction "-_-") (pintype "passive"))
      (node (ref "C13") (pin "2") (pinfunction "2_2") (pintype "passive"))
      (node (ref "C14") (pin "2") (pinfunction "2_2") (pintype "passive"))
      (node (ref "C15") (pin "-") (pinfunction "-_-") (pintype "passive"))
      (node (ref "C16") (pin "2") (pinfunction "2_2") (pintype "passive"))
      (node (ref "C17") (pin "2") (pinfunction "2_2") (pintype "passive"))
      (node (ref "C18") (pin "2") (pinfunction "2_2") (pintype "passive"))
      (node (ref "C19") (pin "2") (pinfunction "2_2") (pintype "passive"))
      (node (ref "C2") (pin "2") (pinfunction "2_2") (pintype "passive"))
      (node (ref "C20") (pin "1") (pinfunction "1_1") (pintype "passive"))
      (node (ref "C21") (pin "2") (pinfunction "2_2") (pintype "passive"))
      (node (ref "C22") (pin "2") (pinfunction "2_2") (pintype "passive"))
      (node (ref "C23") (pin "1") (pinfunction "1_1") (pintype "passive"))
      (node (ref "C24") (pin "2") (pinfunction "2_2") (pintype "passive"))
      (node (ref "C25") (pin "2") (pinfunction "2_2") (pintype "passive"))
      (node (ref "C26") (pin "-") (pinfunction "-_-") (pintype "passive"))
      (node (ref "C27") (pin "2") (pinfunction "2_2") (pintype "passive"))
      (node (ref "C28") (pin "2") (pinfunction "2_2") (pintype "passive"))
      (node (ref "C29") (pin "2") (pinfunction "2_2") (pintype "passive"))
      (node (ref "C3") (pin "2") (pinfunction "2_2") (pintype "passive"))
      (node (ref "C30") (pin "-") (pinfunction "-_-") (pintype "passive"))
      (node (ref "C31") (pin "2") (pinfunction "2_2") (pintype "passive"))
      (node (ref "C32") (pin "2") (pinfunction "2_2") (pintype "passive"))
      (node (ref "C38") (pin "2") (pinfunction "2_2") (pintype "passive"))
      (node (ref "C4") (pin "2") (pinfunction "2_2") (pintype "passive"))
      (node (ref "C40") (pin "2") (pinfunction "2_2") (pintype "passive"))
      (node (ref "C41") (pin "2") (pinfunction "2_2") (pintype "passive"))
      (node (ref "C42") (pin "2") (pinfunction "2_2") (pintype "passive"))
      (node (ref "C45") (pin "2") (pinfunction "2_2") (pintype "passive"))
      (node (ref "C46") (pin "2") (pinfunction "2_2") (pintype "passive"))
      (node (ref "C47") (pin "2") (pinfunction "2_2") (pintype "passive"))
      (node (ref "C48") (pin "2") (pinfunction "2_2") (pintype "passive"))
      (node (ref "C49") (pin "2") (pinfunction "2_2") (pintype "passive"))
      (node (ref "C5") (pin "-") (pinfunction "-_-") (pintype "passive"))
      (node (ref "C50") (pin "2") (pinfunction "2_2") (pintype "passive"))
      (node (ref "C51") (pin "-") (pinfunction "-_-") (pintype "passive"))
      (node (ref "C52") (pin "-") (pinfunction "-_-") (pintype "passive"))
      (node (ref "C53") (pin "2") (pinfunction "2_2") (pintype "passive"))
      (node (ref "C54") (pin "2") (pinfunction "2_2") (pintype "passive"))
      (node (ref "C55") (pin "2") (pinfunction "2_2") (pintype "passive"))
      (node (ref "C56") (pin "2") (pinfunction "2_2") (pintype "passive"))
      (node (ref "C57") (pin "2") (pinfunction "2_2") (pintype "passive"))
      (node (ref "C59") (pin "2") (pinfunction "2_2") (pintype "passive"))
      (node (ref "C6") (pin "2") (pinfunction "2_2") (pintype "passive"))
      (node (ref "C60") (pin "2") (pinfunction "2_2") (pintype "passive"))
      (node (ref "C7") (pin "2") (pinfunction "2_2") (pintype "passive"))
      (node (ref "C8") (pin "2") (pinfunction "2_2") (pintype "passive"))
      (node (ref "C9") (pin "2") (pinfunction "2_2") (pintype "passive"))
      (node (ref "IC1") (pin "2") (pinfunction "GND_2") (pintype "bidirectional"))
      (node (ref "IC2") (pin "1") (pinfunction "GND_1") (pintype "input"))
      (node (ref "IC4") (pin "15") (pinfunction "CDVSS_15") (pintype "power_in"))
      (node (ref "IC4") (pin "19") (pinfunction "ANA18VSS_19") (pintype "power_in"))
      (node (ref "IC4") (pin "35") (pinfunction "IO_VSS2_35") (pintype "power_in"))
      (node (ref "IC4") (pin "36") (pinfunction "CORE_VSS_36") (pintype "power_in"))
      (node (ref "IC4") (pin "47") (pinfunction "IO_VSS1_47") (pintype "power_in"))
      (node (ref "IC4") (pin "6") (pinfunction "TXD_3_6") (pintype "bidirectional"))
      (node (ref "IC5") (pin "1") (pinfunction "GND_1") (pintype "input"))
      (node (ref "JP2") (pin "3") (pinfunction "3_3") (pintype "passive"))
      (node (ref "JP3") (pin "1") (pinfunction "1_1") (pintype "passive"))
      (node (ref "JP5") (pin "GND1") (pinfunction "GND_GND1") (pintype "bidirectional"))
      (node (ref "R21") (pin "1") (pinfunction "1_1") (pintype "passive"))
      (node (ref "R26") (pin "2") (pinfunction "2_2") (pintype "passive"))
      (node (ref "R27") (pin "2") (pinfunction "2_2") (pintype "passive"))
      (node (ref "R28") (pin "2") (pinfunction "2_2") (pintype "passive"))
      (node (ref "R29") (pin "2") (pinfunction "2_2") (pintype "passive"))
      (node (ref "R36") (pin "2") (pinfunction "2_2") (pintype "passive"))
      (node (ref "R6") (pin "2") (pinfunction "2_2") (pintype "passive"))
      (node (ref "RJ1") (pin "GND") (pinfunction "GND_GND") (pintype "bidirectional"))
      (node (ref "RJ1") (pin "SHIELD0") (pinfunction "SHIELD0_SHIELD0") (pintype "bidirectional"))
      (node (ref "RJ1") (pin "SHIELD1") (pinfunction "SHIELD1_SHIELD1") (pintype "bidirectional"))
      (node (ref "SV1") (pin "29") (pinfunction "29_29") (pintype "passive"))
      (node (ref "SV1") (pin "30") (pinfunction "30_30") (pintype "passive"))
      (node (ref "U$1") (pin "2") (pinfunction "GND_2") (pintype "power_in"))
      (node (ref "U$2") (pin "4") (pinfunction "VSS_4") (pintype "bidirectional"))
      (node (ref "U$3") (pin "13") (pinfunction "VSS_13") (pintype "bidirectional"))
      (node (ref "U$3") (pin "31") (pinfunction "AVSS_31") (pintype "bidirectional"))
      (node (ref "U$3") (pin "36") (pinfunction "VSS_36") (pintype "bidirectional"))
      (node (ref "U$3") (pin "45") (pinfunction "VSS_45") (pintype "bidirectional"))
      (node (ref "U$3") (pin "53") (pinfunction "VSS_53") (pintype "bidirectional"))
      (node (ref "U$3") (pin "63") (pinfunction "VSS_63") (pintype "bidirectional"))
      (node (ref "U$3") (pin "75") (pinfunction "VSS_75") (pintype "bidirectional"))
      (node (ref "U$3") (pin "84") (pinfunction "VSS_84") (pintype "bidirectional"))
      (node (ref "U$3") (pin "92") (pinfunction "VSS_92") (pintype "bidirectional"))
      (node (ref "U$7") (pin "2") (pinfunction "GND_2") (pintype "power_in"))
      (node (ref "U1") (pin "6") (pinfunction "GND_6") (pintype "bidirectional"))
      (node (ref "U1") (pin "CD2") (pinfunction "SHIELD_CD2") (pintype "bidirectional"))
      (node (ref "U1") (pin "GND1") (pinfunction "SHIELD_GND1") (pintype "bidirectional"))
      (node (ref "U1") (pin "GND2") (pinfunction "SHIELD_GND2") (pintype "bidirectional"))
      (node (ref "U2") (pin "16") (pinfunction "DGND1_16") (pintype "power_in"))
      (node (ref "U2") (pin "20") (pinfunction "DGND2_20") (pintype "power_in"))
      (node (ref "U2") (pin "21") (pinfunction "DGND3_21") (pintype "power_in"))
      (node (ref "U2") (pin "22") (pinfunction "DGND4_22") (pintype "power_in"))
      (node (ref "U2") (pin "4") (pinfunction "DGND_4") (pintype "power_in"))
      (node (ref "X1") (pin "2") (pinfunction "S_2") (pintype "passive"))
      (node (ref "X3") (pin "4") (pinfunction "4_4") (pintype "passive"))
      (node (ref "X3") (pin "M1") (pinfunction "S1_M1") (pintype "passive"))
      (node (ref "X3") (pin "M2") (pinfunction "S2_M2") (pintype "passive"))
      (node (ref "Y3") (pin "2") (pinfunction "3_2") (pintype "passive"))
      (node (ref "Y3") (pin "4") (pinfunction "3_4") (pintype "passive"))
    )
    (net (code "20") (name "LED_ACT") (class "Default")
      (node (ref "IC4") (pin "26") (pinfunction "LED_ACTCOL_26") (pintype "bidirectional"))
      (node (ref "RJ1") (pin "G-") (pinfunction "G-_G-") (pintype "bidirectional"))
    )
    (net (code "21") (name "LED_LINK") (class "Default")
      (node (ref "IC4") (pin "28") (pinfunction "LED_LNK_28") (pintype "bidirectional"))
      (node (ref "RJ1") (pin "Y-") (pinfunction "Y-_Y-") (pintype "bidirectional"))
    )
    (net (code "22") (name "MCLR") (class "Default")
      (node (ref "JP2") (pin "1") (pinfunction "1_1") (pintype "passive"))
      (node (ref "R12") (pin "1") (pinfunction "1_1") (pintype "passive"))
      (node (ref "U$3") (pin "15") (pinfunction "MCLR_15") (pintype "bidirectional"))
    )
    (net (code "23") (name "MISO") (class "Default")
      (node (ref "R16") (pin "1") (pinfunction "1_1") (pintype "passive"))
      (node (ref "U$2") (pin "2") (pinfunction "SO_2") (pintype "bidirectional"))
      (node (ref "U$3") (pin "64") (pinfunction "EBIA9/RPF4/SDA5/PMA9/RF4_64") (pintype "bidirectional"))
      (node (ref "U1") (pin "7") (pinfunction "DO_7") (pintype "bidirectional"))
    )
    (net (code "24") (name "MOSI") (class "Default")
      (node (ref "U$2") (pin "5") (pinfunction "SI_5") (pintype "bidirectional"))
      (node (ref "U$3") (pin "47") (pinfunction "AN32/AETXD0/RPD14/RD14_47") (pintype "bidirectional"))
      (node (ref "U1") (pin "3") (pinfunction "DI_3") (pintype "bidirectional"))
    )
    (net (code "25") (name "Net-(C28-Pad1)") (class "Default")
      (node (ref "C28") (pin "1") (pinfunction "1_1") (pintype "passive"))
      (node (ref "R12") (pin "2") (pinfunction "2_2") (pintype "passive"))
      (node (ref "R9") (pin "1") (pinfunction "1_1") (pintype "passive"))
    )
    (net (code "26") (name "Net-(C36-Pad2)") (class "Default")
      (node (ref "C36") (pin "2") (pinfunction "2_2") (pintype "passive"))
      (node (ref "R23") (pin "1") (pinfunction "1_1") (pintype "passive"))
    )
    (net (code "27") (name "Net-(C37-Pad2)") (class "Default")
      (node (ref "C37") (pin "2") (pinfunction "2_2") (pintype "passive"))
      (node (ref "R24") (pin "1") (pinfunction "1_1") (pintype "passive"))
    )
    (net (code "28") (name "Net-(C39-Pad2)") (class "Default")
      (node (ref "C39") (pin "2") (pinfunction "2_2") (pintype "passive"))
      (node (ref "R22") (pin "1") (pinfunction "1_1") (pintype "passive"))
    )
    (net (code "29") (name "Net-(C43-Pad1)") (class "Default")
      (node (ref "C43") (pin "1") (pinfunction "1_1") (pintype "passive"))
      (node (ref "R31") (pin "1") (pinfunction "1_1") (pintype "passive"))
    )
    (net (code "30") (name "Net-(C43-Pad2)") (class "Default")
      (node (ref "C43") (pin "2") (pinfunction "2_2") (pintype "passive"))
      (node (ref "J1") (pin "TIP") (pinfunction "TIP_TIP") (pintype "bidirectional"))
      (node (ref "R34") (pin "1") (pinfunction "1_1") (pintype "passive"))
    )
    (net (code "31") (name "Net-(C44-Pad1)") (class "Default")
      (node (ref "C44") (pin "1") (pinfunction "1_1") (pintype "passive"))
      (node (ref "R32") (pin "1") (pinfunction "1_1") (pintype "passive"))
    )
    (net (code "32") (name "Net-(C44-Pad2)") (class "Default")
      (node (ref "C44") (pin "2") (pinfunction "2_2") (pintype "passive"))
      (node (ref "J1") (pin "RING1") (pinfunction "RING1_RING1") (pintype "bidirectional"))
      (node (ref "R33") (pin "1") (pinfunction "1_1") (pintype "passive"))
    )
    (net (code "33") (name "Net-(IC1-I{slash}O_1)") (class "Default")
      (node (ref "IC1") (pin "1") (pinfunction "I/O_1_1") (pintype "bidirectional"))
      (node (ref "X3") (pin "2") (pinfunction "2_2") (pintype "passive"))
    )
    (net (code "34") (name "Net-(IC1-I{slash}O_2)") (class "Default")
      (node (ref "IC1") (pin "3") (pinfunction "I/O_2_3") (pintype "bidirectional"))
      (node (ref "X3") (pin "3") (pinfunction "3_3") (pintype "passive"))
    )
    (net (code "35") (name "Net-(IC4-IP_PH_M)") (class "Default")
      (node (ref "IC4") (pin "20") (pinfunction "IP_PH_M_20") (pintype "input"))
      (node (ref "R10") (pin "1") (pinfunction "1_1") (pintype "passive"))
    )
    (net (code "36") (name "Net-(IC4-IP_PH_P)") (class "Default")
      (node (ref "IC4") (pin "21") (pinfunction "IP_PH_P_21") (pintype "input"))
      (node (ref "R7") (pin "1") (pinfunction "1_1") (pintype "passive"))
    )
    (net (code "37") (name "Net-(IC4-RX_DV)") (class "Default")
      (node (ref "IC4") (pin "39") (pinfunction "RX_DV_39") (pintype "bidirectional"))
      (node (ref "R20") (pin "2") (pinfunction "2_2") (pintype "passive"))
    )
    (net (code "38") (name "Net-(IC4-VREF)") (class "Default")
      (node (ref "IC4") (pin "24") (pinfunction "VREF_24") (pintype "bidirectional"))
      (node (ref "R6") (pin "1") (pinfunction "1_1") (pintype "passive"))
    )
    (net (code "39") (name "Net-(JP5-VCC)") (class "Default")
      (node (ref "F1") (pin "1") (pinfunction "1_1") (pintype "passive"))
      (node (ref "JP5") (pin "VBUS1") (pinfunction "VCC_VBUS1") (pintype "bidirectional"))
      (node (ref "X1") (pin "1") (pinfunction "S_1") (pintype "passive"))
    )
    (net (code "40") (name "Net-(R42-Pad2)") (class "Default")
      (node (ref "R42") (pin "2") (pinfunction "2_2") (pintype "passive"))
      (node (ref "RJ1") (pin "G+") (pinfunction "G+_G+") (pintype "bidirectional"))
    )
    (net (code "41") (name "Net-(R43-Pad1)") (class "Default")
      (node (ref "R43") (pin "1") (pinfunction "1_1") (pintype "passive"))
      (node (ref "RJ1") (pin "Y+") (pinfunction "Y+_Y+") (pintype "bidirectional"))
    )
    (net (code "42") (name "Net-(U2A-GBUF)") (class "Default")
      (node (ref "R23") (pin "2") (pinfunction "2_2") (pintype "passive"))
      (node (ref "U2") (pin "42") (pinfunction "GBUF_42") (pintype "bidirectional"))
    )
    (net (code "43") (name "Net-(U2A-GPIO0)") (class "Default")
      (node (ref "R26") (pin "1") (pinfunction "1_1") (pintype "passive"))
      (node (ref "U2") (pin "33") (pinfunction "GPIO0_33") (pintype "bidirectional"))
    )
    (net (code "44") (name "Net-(U2A-GPIO1)") (class "Default")
      (node (ref "R27") (pin "1") (pinfunction "1_1") (pintype "passive"))
      (node (ref "U2") (pin "34") (pinfunction "GPIO1_34") (pintype "bidirectional"))
    )
    (net (code "45") (name "Net-(U2A-GPIO2{slash}DCLK)") (class "Default")
      (node (ref "R28") (pin "1") (pinfunction "1_1") (pintype "passive"))
      (node (ref "U2") (pin "9") (pinfunction "GPIO2/DCLK_9") (pintype "bidirectional"))
    )
    (net (code "46") (name "Net-(U2A-GPIO3{slash}SDATA)") (class "Default")
      (node (ref "R29") (pin "1") (pinfunction "1_1") (pintype "passive"))
      (node (ref "U2") (pin "10") (pinfunction "GPIO3/SDATA_10") (pintype "bidirectional"))
    )
    (net (code "47") (name "Net-(U2A-LEFT)") (class "Default")
      (node (ref "R22") (pin "2") (pinfunction "2_2") (pintype "passive"))
      (node (ref "R31") (pin "2") (pinfunction "2_2") (pintype "passive"))
      (node (ref "U2") (pin "46") (pinfunction "LEFT_46") (pintype "bidirectional"))
    )
    (net (code "48") (name "Net-(U2A-RCAP)") (class "Default")
      (node (ref "R25") (pin "2") (pinfunction "2_2") (pintype "passive"))
      (node (ref "U2") (pin "44") (pinfunction "RCAP_44") (pintype "bidirectional"))
    )
    (net (code "49") (name "Net-(U2A-RIGHT)") (class "Default")
      (node (ref "R24") (pin "2") (pinfunction "2_2") (pintype "passive"))
      (node (ref "R32") (pin "2") (pinfunction "2_2") (pintype "passive"))
      (node (ref "U2") (pin "39") (pinfunction "RIGHT_39") (pintype "bidirectional"))
    )
    (net (code "50") (name "Net-(U2A-RX)") (class "Default")
      (node (ref "R30") (pin "1") (pinfunction "1_1") (pintype "passive"))
      (node (ref "U2") (pin "26") (pinfunction "RX_26") (pintype "bidirectional"))
    )
    (net (code "51") (name "Net-(U2A-XTALI)") (class "Default")
      (node (ref "C50") (pin "1") (pinfunction "1_1") (pintype "passive"))
      (node (ref "R35") (pin "2") (pinfunction "2_2") (pintype "passive"))
      (node (ref "U2") (pin "18") (pinfunction "XTALI_18") (pintype "bidirectional"))
      (node (ref "Y3") (pin "1") (pinfunction "2_1") (pintype "passive"))
    )
    (net (code "52") (name "Net-(U2A-XTALO)") (class "Default")
      (node (ref "C49") (pin "1") (pinfunction "1_1") (pintype "passive"))
      (node (ref "R35") (pin "1") (pinfunction "1_1") (pintype "passive"))
      (node (ref "U2") (pin "17") (pinfunction "XTALO_17") (pintype "bidirectional"))
      (node (ref "Y3") (pin "3") (pinfunction "1_3") (pintype "passive"))
    )
    (net (code "53") (name "PGEC") (class "Default")
      (node (ref "JP2") (pin "5") (pinfunction "5_5") (pintype "passive"))
      (node (ref "U$3") (pin "24") (pinfunction "PGEC1/AN1/RPB1/RB1_24") (pintype "bidirectional"))
    )
    (net (code "54") (name "PGED") (class "Default")
      (node (ref "JP2") (pin "4") (pinfunction "4_4") (pintype "passive"))
      (node (ref "U$3") (pin "25") (pinfunction "PGED1/AN0/RPB0/RB0_25") (pintype "bidirectional"))
    )
    (net (code "55") (name "PH0") (class "Default")
      (node (ref "U$1") (pin "3") (pinfunction "OUT_3") (pintype "output"))
      (node (ref "U$3") (pin "49") (pinfunction "OSC1/CLKI/RC12_49") (pintype "bidirectional"))
    )
    (net (code "56") (name "RA2") (class "Default")
      (node (ref "SV1") (pin "4") (pinfunction "4_4") (pintype "passive"))
      (node (ref "U$3") (pin "59") (pinfunction "EBICS0/SCL2/RA2_59") (pintype "bidirectional"))
    )
    (net (code "57") (name "RA3") (class "Default")
      (node (ref "SV1") (pin "3") (pinfunction "3_3") (pintype "passive"))
      (node (ref "U$3") (pin "60") (pinfunction "EBIRDY1/SDA2/RA3_60") (pintype "bidirectional"))
    )
    (net (code "58") (name "RA4") (class "Default")
      (node (ref "SV1") (pin "6") (pinfunction "6_6") (pintype "passive"))
      (node (ref "U$3") (pin "61") (pinfunction "EBIA14/PMCS1/PMA14/RA4_61") (pintype "bidirectional"))
    )
    (net (code "59") (name "RA5") (class "Default")
      (node (ref "SV1") (pin "28") (pinfunction "28_28") (pintype "passive"))
      (node (ref "U$3") (pin "2") (pinfunction "EBIA5/AN34/PMA5/RA5_2") (pintype "bidirectional"))
    )
    (net (code "60") (name "RA6") (class "Default")
      (node (ref "SV1") (pin "15") (pinfunction "15_15") (pintype "passive"))
      (node (ref "U$3") (pin "89") (pinfunction "TRCLK/SQICLK/RA6_89") (pintype "bidirectional"))
    )
    (net (code "61") (name "RA7") (class "Default")
      (node (ref "SV1") (pin "18") (pinfunction "18_18") (pintype "passive"))
      (node (ref "U$3") (pin "90") (pinfunction "TRD3/SQID3/RA7_90") (pintype "bidirectional"))
    )
    (net (code "62") (name "RA14") (class "Default")
      (node (ref "SV1") (pin "5") (pinfunction "5_5") (pintype "passive"))
      (node (ref "U$3") (pin "66") (pinfunction "AETXCLK/RPA14/SCL1/RA14_66") (pintype "bidirectional"))
    )
    (net (code "63") (name "RD1") (class "Default")
      (node (ref "SV1") (pin "7") (pinfunction "7_7") (pintype "passive"))
      (node (ref "U$3") (pin "76") (pinfunction "RPD1/SCK1/RD1_76") (pintype "bidirectional"))
    )
    (net (code "64") (name "RD3") (class "Default")
      (node (ref "SV1") (pin "10") (pinfunction "10_10") (pintype "passive"))
      (node (ref "U$3") (pin "78") (pinfunction "EBID15/ETXCLK/RPD3/PMD15/RD3_78") (pintype "bidirectional"))
    )
    (net (code "65") (name "RD4") (class "Default")
      (node (ref "SV1") (pin "11") (pinfunction "11_11") (pintype "passive"))
      (node (ref "U$3") (pin "81") (pinfunction "SQICS0/RPD4/RD4_81") (pintype "bidirectional"))
    )
    (net (code "66") (name "RD5") (class "Default")
      (node (ref "SV1") (pin "14") (pinfunction "14_14") (pintype "passive"))
      (node (ref "U$3") (pin "82") (pinfunction "SQICS1/RPD5/RD5_82") (pintype "bidirectional"))
    )
    (net (code "67") (name "RD9") (class "Default")
      (node (ref "SV1") (pin "8") (pinfunction "8_8") (pintype "passive"))
      (node (ref "U$3") (pin "68") (pinfunction "EBIA15/RPD9/PMCS2/PMA15/RD9_68") (pintype "bidirectional"))
    )
    (net (code "68") (name "RD12") (class "Default")
      (node (ref "SV1") (pin "9") (pinfunction "9_9") (pintype "passive"))
      (node (ref "U$3") (pin "79") (pinfunction "EBID12/ETXD2/RPD12/PMD12/RD12_79") (pintype "bidirectional"))
    )
    (net (code "69") (name "RD13") (class "Default")
      (node (ref "SV1") (pin "12") (pinfunction "12_12") (pintype "passive"))
      (node (ref "U$3") (pin "80") (pinfunction "EBID13/ETXD3/PMD13/RD13_80") (pintype "bidirectional"))
    )
    (net (code "70") (name "RD_N") (class "Default")
      (node (ref "IC4") (pin "13") (pinfunction "TPRDM_13") (pintype "bidirectional"))
      (node (ref "R5") (pin "1") (pinfunction "1_1") (pintype "passive"))
      (node (ref "RJ1") (pin "RD-") (pinfunction "RD-_RD-") (pintype "bidirectional"))
    )
    (net (code "71") (name "RD_P") (class "Default")
      (node (ref "IC4") (pin "14") (pinfunction "TPRDP_14") (pintype "bidirectional"))
      (node (ref "R4") (pin "1") (pinfunction "1_1") (pintype "passive"))
      (node (ref "RJ1") (pin "RD+") (pinfunction "RD+_RD+") (pintype "bidirectional"))
    )
    (net (code "72") (name "RE0") (class "Default")
      (node (ref "SV1") (pin "17") (pinfunction "17_17") (pintype "passive"))
      (node (ref "U$3") (pin "91") (pinfunction "EBID0/PMD0/RE0_91") (pintype "bidirectional"))
    )
    (net (code "73") (name "RE1") (class "Default")
      (node (ref "SV1") (pin "20") (pinfunction "20_20") (pintype "passive"))
      (node (ref "U$3") (pin "94") (pinfunction "EBID1/PMD1/RE1_94") (pintype "bidirectional"))
    )
    (net (code "74") (name "RE2") (class "Default")
      (node (ref "SV1") (pin "24") (pinfunction "24_24") (pintype "passive"))
      (node (ref "U$3") (pin "98") (pinfunction "EBID2/PMD2/RE2_98") (pintype "bidirectional"))
    )
    (net (code "75") (name "RE3") (class "Default")
      (node (ref "SV1") (pin "23") (pinfunction "23_23") (pintype "passive"))
      (node (ref "U$3") (pin "99") (pinfunction "EBID3/RPE3/PMD3/RE3_99") (pintype "bidirectional"))
    )
    (net (code "76") (name "RE4") (class "Default")
      (node (ref "SV1") (pin "26") (pinfunction "26_26") (pintype "passive"))
      (node (ref "U$3") (pin "100") (pinfunction "EBID4/AN18/PMD4/RE4_100") (pintype "bidirectional"))
    )
    (net (code "77") (name "RE5") (class "Default")
      (node (ref "SV1") (pin "27") (pinfunction "27_27") (pintype "passive"))
      (node (ref "U$3") (pin "3") (pinfunction "EBID5/AN17/RPE5/PMD5/RE5_3") (pintype "bidirectional"))
    )
    (net (code "78") (name "REG_OUT") (class "Default")
      (node (ref "C18") (pin "1") (pinfunction "1_1") (pintype "passive"))
      (node (ref "C19") (pin "1") (pinfunction "1_1") (pintype "passive"))
      (node (ref "C24") (pin "1") (pinfunction "1_1") (pintype "passive"))
      (node (ref "C32") (pin "1") (pinfunction "1_1") (pintype "passive"))
      (node (ref "IC4") (pin "18") (pinfunction "ANA18VDD_18") (pintype "power_in"))
      (node (ref "IC4") (pin "23") (pinfunction "REG_OUT_23") (pintype "output"))
      (node (ref "IC4") (pin "37") (pinfunction "CORE_VDD_37") (pintype "power_in"))
    )
    (net (code "79") (name "RG0") (class "Default")
      (node (ref "SV1") (pin "16") (pinfunction "16_16") (pintype "passive"))
      (node (ref "U$3") (pin "88") (pinfunction "EBID8/RPG0/PMD8/RG0_88") (pintype "bidirectional"))
    )
    (net (code "80") (name "RG1") (class "Default")
      (node (ref "SV1") (pin "13") (pinfunction "13_13") (pintype "passive"))
      (node (ref "U$3") (pin "87") (pinfunction "EBID9/ETXERR/RPG1/PMD9/RG1_87") (pintype "bidirectional"))
    )
    (net (code "81") (name "RG12") (class "Default")
      (node (ref "SV1") (pin "22") (pinfunction "22_22") (pintype "passive"))
      (node (ref "U$3") (pin "96") (pinfunction "TRD1/SQID1/RG12_96") (pintype "bidirectional"))
    )
    (net (code "82") (name "RG13") (class "Default")
      (node (ref "SV1") (pin "21") (pinfunction "21_21") (pintype "passive"))
      (node (ref "U$3") (pin "97") (pinfunction "TRD0/SQID0/RG13_97") (pintype "bidirectional"))
    )
    (net (code "83") (name "RG14") (class "Default")
      (node (ref "SV1") (pin "19") (pinfunction "19_19") (pintype "passive"))
      (node (ref "U$3") (pin "95") (pinfunction "TRD2/SQID2/RG14_95") (pintype "bidirectional"))
    )
    (net (code "84") (name "RG15") (class "Default")
      (node (ref "SV1") (pin "25") (pinfunction "25_25") (pintype "passive"))
      (node (ref "U$3") (pin "1") (pinfunction "AN23/AERXERR/RG15_1") (pintype "bidirectional"))
    )
    (net (code "85") (name "SCK") (class "Default")
      (node (ref "U$2") (pin "6") (pinfunction "SCK_6") (pintype "bidirectional"))
      (node (ref "U$3") (pin "39") (pinfunction "TDI/EBIA18/AN30/RPF13/SCK5/RF13_39") (pintype "bidirectional"))
      (node (ref "U1") (pin "5") (pinfunction "SCK_5") (pintype "bidirectional"))
    )
    (net (code "86") (name "SCL") (class "Default")
      (node (ref "SV1") (pin "1") (pinfunction "1_1") (pintype "passive"))
      (node (ref "U$3") (pin "58") (pinfunction "EBIRDY2/RPF8/SCL3/RF8_58") (pintype "bidirectional"))
    )
    (net (code "87") (name "SDA") (class "Default")
      (node (ref "SV1") (pin "2") (pinfunction "2_2") (pintype "passive"))
      (node (ref "U$3") (pin "57") (pinfunction "EBIRDY3/RPF2/SDA3/RF2_57") (pintype "bidirectional"))
    )
    (net (code "88") (name "SD_CS") (class "Default")
      (node (ref "R11") (pin "1") (pinfunction "1_1") (pintype "passive"))
      (node (ref "U$3") (pin "44") (pinfunction "EBIA0/AN10/ERXD3/AETXD2/RPB15/OCFB/PMA0/RB15_44") (pintype "bidirectional"))
      (node (ref "U1") (pin "2") (pinfunction "CS_2") (pintype "bidirectional"))
    )
    (net (code "89") (name "SD_PRESENT") (class "Default")
      (node (ref "R8") (pin "1") (pinfunction "1_1") (pintype "passive"))
      (node (ref "U$3") (pin "56") (pinfunction "RPF3/USBID/RF3_56") (pintype "bidirectional"))
      (node (ref "U1") (pin "CD1") (pinfunction "SHIELD_CD1") (pintype "bidirectional"))
    )
    (net (code "90") (name "SOSCI") (class "Default")
      (node (ref "C20") (pin "2") (pinfunction "2_2") (pintype "passive"))
      (node (ref "U$3") (pin "72") (pinfunction "SOSCI/RPC13/RC13_72") (pintype "bidirectional"))
      (node (ref "X2") (pin "1") (pinfunction "1_1") (pintype "passive"))
    )
    (net (code "91") (name "SOSCO") (class "Default")
      (node (ref "C23") (pin "2") (pinfunction "2_2") (pintype "passive"))
      (node (ref "U$3") (pin "73") (pinfunction "SOSCO/RPC14/T1CK/RC14_73") (pintype "bidirectional"))
      (node (ref "X2") (pin "2") (pinfunction "2_2") (pintype "passive"))
    )
    (net (code "92") (name "TD_N") (class "Default")
      (node (ref "IC4") (pin "16") (pinfunction "TPTDM_16") (pintype "bidirectional"))
      (node (ref "R3") (pin "1") (pinfunction "1_1") (pintype "passive"))
      (node (ref "RJ1") (pin "TD-") (pinfunction "TD-_TD-") (pintype "bidirectional"))
    )
    (net (code "93") (name "TD_P") (class "Default")
      (node (ref "IC4") (pin "17") (pinfunction "TPTDP_17") (pintype "bidirectional"))
      (node (ref "R2") (pin "1") (pinfunction "1_1") (pintype "passive"))
      (node (ref "RJ1") (pin "TD+") (pinfunction "TD+_TD+") (pintype "bidirectional"))
    )
    (net (code "94") (name "U2_RX") (class "Default")
      (node (ref "JP3") (pin "3") (pinfunction "3_3") (pintype "passive"))
      (node (ref "U$3") (pin "32") (pinfunction "EBIA10/AN48/RPB8/PMA10/RB8_32") (pintype "bidirectional"))
    )
    (net (code "95") (name "U2_TX") (class "Default")
      (node (ref "JP3") (pin "2") (pinfunction "2_2") (pintype "passive"))
      (node (ref "U$3") (pin "26") (pinfunction "PGEC2/AN46/RPB6/RB6_26") (pintype "bidirectional"))
    )
    (net (code "96") (name "VBUS") (class "Default")
      (node (ref "C12") (pin "+") (pinfunction "+_+") (pintype "passive"))
      (node (ref "C13") (pin "1") (pinfunction "1_1") (pintype "passive"))
      (node (ref "C27") (pin "1") (pinfunction "1_1") (pintype "passive"))
      (node (ref "C30") (pin "+") (pinfunction "+_+") (pintype "passive"))
      (node (ref "C5") (pin "+") (pinfunction "+_+") (pintype "passive"))
      (node (ref "C52") (pin "+") (pinfunction "+_+") (pintype "passive"))
      (node (ref "C53") (pin "1") (pinfunction "1_1") (pintype "passive"))
      (node (ref "F1") (pin "2") (pinfunction "2_2") (pintype "passive"))
      (node (ref "IC1") (pin "5") (pinfunction "VBUS_5") (pintype "bidirectional"))
      (node (ref "IC2") (pin "3") (pinfunction "IN_3") (pintype "input"))
      (node (ref "IC5") (pin "3") (pinfunction "IN_3") (pintype "input"))
      (node (ref "SV1") (pin "31") (pinfunction "31_31") (pintype "passive"))
      (node (ref "SV1") (pin "32") (pinfunction "32_32") (pintype "passive"))
      (node (ref "U$3") (pin "51") (pinfunction "VBUS_51") (pintype "bidirectional"))
      (node (ref "X3") (pin "1") (pinfunction "1_1") (pintype "passive"))
    )
    (net (code "97") (name "VS_AGND") (class "Default")
      (node (ref "C33") (pin "2") (pinfunction "2_2") (pintype "passive"))
      (node (ref "C34") (pin "2") (pinfunction "2_2") (pintype "passive"))
      (node (ref "C35") (pin "2") (pinfunction "2_2") (pintype "passive"))
      (node (ref "C36") (pin "1") (pinfunction "1_1") (pintype "passive"))
      (node (ref "C37") (pin "1") (pinfunction "1_1") (pintype "passive"))
      (node (ref "C39") (pin "1") (pinfunction "1_1") (pintype "passive"))
      (node (ref "C58") (pin "2") (pinfunction "2_2") (pintype "passive"))
      (node (ref "J1") (pin "EARTH") (pinfunction "EARTH_EARTH") (pintype "bidirectional"))
      (node (ref "R21") (pin "2") (pinfunction "2_2") (pintype "passive"))
      (node (ref "R25") (pin "1") (pinfunction "1_1") (pintype "passive"))
      (node (ref "R33") (pin "2") (pinfunction "2_2") (pintype "passive"))
      (node (ref "R34") (pin "2") (pinfunction "2_2") (pintype "passive"))
      (node (ref "U2") (pin "37") (pinfunction "AGND_37") (pintype "power_in"))
      (node (ref "U2") (pin "40") (pinfunction "AGND1_40") (pintype "power_in"))
      (node (ref "U2") (pin "41") (pinfunction "AGND2_41") (pintype "power_in"))
      (node (ref "U2") (pin "47") (pinfunction "AGND3_47") (pintype "power_in"))
    )
    (net (code "98") (name "VS_AVDD") (class "Default")
      (node (ref "C33") (pin "1") (pinfunction "1_1") (pintype "passive"))
      (node (ref "C34") (pin "1") (pinfunction "1_1") (pintype "passive"))
      (node (ref "C35") (pin "1") (pinfunction "1_1") (pintype "passive"))
      (node (ref "C58") (pin "1") (pinfunction "1_1") (pintype "passive"))
      (node (ref "L1") (pin "1") (pinfunction "1_1") (pintype "passive"))
      (node (ref "U2") (pin "38") (pinfunction "AVDD_38") (pintype "power_in"))
      (node (ref "U2") (pin "43") (pinfunction "AVDD1_43") (pintype "power_in"))
      (node (ref "U2") (pin "45") (pinfunction "AVDD2_45") (pintype "power_in"))
    )
    (net (code "99") (name "VS_CVDD") (class "Default")
      (node (ref "C45") (pin "1") (pinfunction "1_1") (pintype "passive"))
      (node (ref "C46") (pin "1") (pinfunction "1_1") (pintype "passive"))
      (node (ref "C47") (pin "1") (pinfunction "1_1") (pintype "passive"))
      (node (ref "C48") (pin "1") (pinfunction "1_1") (pintype "passive"))
      (node (ref "C57") (pin "1") (pinfunction "1_1") (pintype "passive"))
      (node (ref "L2") (pin "1") (pinfunction "1_1") (pintype "passive"))
      (node (ref "U2") (pin "24") (pinfunction "CVDD2_24") (pintype "power_in"))
      (node (ref "U2") (pin "31") (pinfunction "CVDD3_31") (pintype "power_in"))
      (node (ref "U2") (pin "5") (pinfunction "CVDD_5") (pintype "power_in"))
      (node (ref "U2") (pin "7") (pinfunction "CVDD1_7") (pintype "power_in"))
    )
    (net (code "100") (name "VS_DREQ") (class "Default")
      (node (ref "U$3") (pin "6") (pinfunction "EBIA6/AN22/RPC1/PMA6/RC1_6") (pintype "bidirectional"))
      (node (ref "U2") (pin "8") (pinfunction "DREQ_8") (pintype "bidirectional"))
    )
    (net (code "101") (name "VS_MISO") (class "Default")
      (node (ref "U$3") (pin "65") (pinfunction "EBIA8/RPF5/SCL5/PMA8/RF5_65") (pintype "bidirectional"))
      (node (ref "U2") (pin "30") (pinfunction "SO_30") (pintype "bidirectional"))
    )
    (net (code "102") (name "VS_MOSI") (class "Default")
      (node (ref "U$3") (pin "67") (pinfunction "AETXEN/RPA15/SDA1/RA15_67") (pintype "bidirectional"))
      (node (ref "U2") (pin "29") (pinfunction "SI_29") (pintype "bidirectional"))
    )
    (net (code "103") (name "VS_SCK") (class "Default")
      (node (ref "U$3") (pin "69") (pinfunction "RPD10/SCK4/RD10_69") (pintype "bidirectional"))
      (node (ref "U2") (pin "28") (pinfunction "SCLK_28") (pintype "bidirectional"))
    )
    (net (code "104") (name "VS_XCS") (class "Default")
      (node (ref "U$3") (pin "5") (pinfunction "EBID7/AN15/PMD7/RE7_5") (pintype "bidirectional"))
      (node (ref "U2") (pin "23") (pinfunction "XCS_23") (pintype "bidirectional"))
    )
    (net (code "105") (name "VS_XDCS") (class "Default")
      (node (ref "U$3") (pin "4") (pinfunction "EBID6/AN16/PMD6/RE6_4") (pintype "bidirectional"))
      (node (ref "U2") (pin "13") (pinfunction "XDCS/BSYNC_13") (pintype "bidirectional"))
    )
    (net (code "106") (name "VS_XRST") (class "Default")
      (node (ref "R36") (pin "1") (pinfunction "1_1") (pintype "passive"))
      (node (ref "U$3") (pin "7") (pinfunction "EBIA12/AN21/RPC2/PMA12/RC2_7") (pintype "bidirectional"))
      (node (ref "U2") (pin "3") (pinfunction "XRESET_3") (pintype "bidirectional"))
    )
    (net (code "107") (name "_2V6") (class "Default")
      (node (ref "C51") (pin "+") (pinfunction "+_+") (pintype "passive"))
      (node (ref "C54") (pin "1") (pinfunction "1_1") (pintype "passive"))
      (node (ref "IC5") (pin "2") (pinfunction "OUT_2") (pintype "passive"))
      (node (ref "IC5") (pin "TAB") (pinfunction "OUT1_TAB") (pintype "passive"))
      (node (ref "L1") (pin "2") (pinfunction "2_2") (pintype "passive"))
      (node (ref "L2") (pin "2") (pinfunction "2_2") (pintype "passive"))
    )
    (net (code "108") (name "unconnected-(IC4-CLK2MAC-Pad25)") (class "Default")
      (node (ref "IC4") (pin "25") (pinfunction "CLK2MAC_25") (pintype "bidirectional"))
    )
    (net (code "109") (name "unconnected-(IC4-COL-Pad42)") (class "Default")
      (node (ref "IC4") (pin "42") (pinfunction "COL_42") (pintype "bidirectional"))
    )
    (net (code "110") (name "unconnected-(IC4-LED_SPD-Pad27)") (class "Default")
      (node (ref "IC4") (pin "27") (pinfunction "LED_SPD_27") (pintype "bidirectional"))
    )
    (net (code "111") (name "unconnected-(IC4-RXD_2-Pad45)") (class "Default")
      (node (ref "IC4") (pin "45") (pinfunction "RXD_2_45") (pintype "bidirectional"))
    )
    (net (code "112") (name "unconnected-(IC4-RXD_3-Pad46)") (class "Default")
      (node (ref "IC4") (pin "46") (pinfunction "RXD_3_46") (pintype "bidirectional"))
    )
    (net (code "113") (name "unconnected-(IC4-RX_CLK-Pad38)") (class "Default")
      (node (ref "IC4") (pin "38") (pinfunction "RX_CLK_38") (pintype "bidirectional"))
    )
    (net (code "114") (name "unconnected-(IC4-TCK-Pad8)") (class "Default")
      (node (ref "IC4") (pin "8") (pinfunction "TCK_8") (pintype "input"))
    )
    (net (code "115") (name "unconnected-(IC4-TDI-Pad12)") (class "Default")
      (node (ref "IC4") (pin "12") (pinfunction "TDI_12") (pintype "input"))
    )
    (net (code "116") (name "unconnected-(IC4-TDO-Pad9)") (class "Default")
      (node (ref "IC4") (pin "9") (pinfunction "TDO_9") (pintype "output"))
    )
    (net (code "117") (name "unconnected-(IC4-TMS-Pad10)") (class "Default")
      (node (ref "IC4") (pin "10") (pinfunction "TMS_10") (pintype "input"))
    )
    (net (code "118") (name "unconnected-(IC4-TRST_N-Pad11)") (class "Default")
      (node (ref "IC4") (pin "11") (pinfunction "TRST_N_11") (pintype "input"))
    )
    (net (code "119") (name "unconnected-(IC4-TXD_2-Pad5)") (class "Default")
      (node (ref "IC4") (pin "5") (pinfunction "TXD_2_5") (pintype "bidirectional"))
    )
    (net (code "120") (name "unconnected-(IC4-TX_CLK-Pad1)") (class "Default")
      (node (ref "IC4") (pin "1") (pinfunction "TX_CLK_1") (pintype "bidirectional"))
    )
    (net (code "121") (name "unconnected-(IC4-X2-Pad33)") (class "Default")
      (node (ref "IC4") (pin "33") (pinfunction "X2_33") (pintype "output"))
    )
    (net (code "122") (name "unconnected-(J1-PadRING2)") (class "Default")
      (node (ref "J1") (pin "RING2") (pinfunction "RING2_RING2") (pintype "bidirectional"))
    )
    (net (code "123") (name "unconnected-(JP2-Pad2)") (class "Default")
      (node (ref "JP2") (pin "2") (pinfunction "2_2") (pintype "passive"))
    )
    (net (code "124") (name "unconnected-(JP2-Pad6)") (class "Default")
      (node (ref "JP2") (pin "6") (pinfunction "6_6") (pintype "passive"))
    )
    (net (code "125") (name "unconnected-(JP5-D+-PadD+1)") (class "Default")
      (node (ref "JP5") (pin "D+1") (pinfunction "D+_D+1") (pintype "bidirectional"))
    )
    (net (code "126") (name "unconnected-(JP5-D--PadD-1)") (class "Default")
      (node (ref "JP5") (pin "D-1") (pinfunction "D-_D-1") (pintype "bidirectional"))
    )
    (net (code "127") (name "unconnected-(JP5-ID-PadID1)") (class "Default")
      (node (ref "JP5") (pin "ID1") (pinfunction "ID_ID1") (pintype "bidirectional"))
    )
    (net (code "128") (name "unconnected-(RJ1-PadNC)") (class "Default")
      (node (ref "RJ1") (pin "NC") (pinfunction "NC_NC") (pintype "bidirectional"))
    )
    (net (code "129") (name "unconnected-(U$1-TRI-Pad1)") (class "Default")
      (node (ref "U$1") (pin "1") (pinfunction "TRI_1") (pintype "input"))
    )
    (net (code "130") (name "unconnected-(U$3-AN2{slash}C2INB{slash}RPB2{slash}RB2-Pad23)") (class "Default")
      (node (ref "U$3") (pin "23") (pinfunction "AN2/C2INB/RPB2/RB2_23") (pintype "bidirectional"))
    )
    (net (code "131") (name "unconnected-(U$3-AN3{slash}C2INA{slash}RPB3{slash}RB3-Pad22)") (class "Default")
      (node (ref "U$3") (pin "22") (pinfunction "AN3/C2INA/RPB3/RB3_22") (pintype "bidirectional"))
    )
    (net (code "132") (name "unconnected-(U$3-AN4{slash}C1INB{slash}RB4-Pad21)") (class "Default")
      (node (ref "U$3") (pin "21") (pinfunction "AN4/C1INB/RB4_21") (pintype "bidirectional"))
    )
    (net (code "133") (name "unconnected-(U$3-AN14{slash}C1IND{slash}ECOL{slash}RPG6{slash}SCK2{slash}RG6-Pad10)") (class "Default")
      (node (ref "U$3") (pin "10") (pinfunction "AN14/C1IND/ECOL/RPG6/SCK2/RG6_10") (pintype "bidirectional"))
    )
    (net (code "134") (name "unconnected-(U$3-AN25{slash}AERXD0{slash}RPE8{slash}RE8-Pad18)") (class "Default")
      (node (ref "U$3") (pin "18") (pinfunction "AN25/AERXD0/RPE8/RE8_18") (pintype "bidirectional"))
    )
    (net (code "135") (name "unconnected-(U$3-AN26{slash}AERXD1{slash}RPE9{slash}RE9-Pad19)") (class "Default")
      (node (ref "U$3") (pin "19") (pinfunction "AN26/AERXD1/RPE9/RE9_19") (pintype "bidirectional"))
    )
    (net (code "136") (name "unconnected-(U$3-AN33{slash}AETXD1{slash}RPD15{slash}SCK6{slash}RD15-Pad48)") (class "Default")
      (node (ref "U$3") (pin "48") (pinfunction "AN33/AETXD1/RPD15/SCK6/RD15_48") (pintype "bidirectional"))
    )
    (net (code "137") (name "unconnected-(U$3-AN45{slash}C1INA{slash}RPB5{slash}RB5-Pad20)") (class "Default")
      (node (ref "U$3") (pin "20") (pinfunction "AN45/C1INA/RPB5/RB5_20") (pintype "bidirectional"))
    )
    (net (code "138") (name "unconnected-(U$3-EBIA1{slash}AN9{slash}ERXD2{slash}AETXD3{slash}RPB14{slash}SCK3{slash}PMA1{slash}RB14-Pad43)") (class "Default")
      (node (ref "U$3") (pin "43") (pinfunction "EBIA1/AN9/ERXD2/AETXD3/RPB14/SCK3/PMA1/RB14_43") (pintype "bidirectional"))
    )
    (net (code "139") (name "unconnected-(U$3-EBIA4{slash}AN13{slash}C1INC{slash}ECRS{slash}RPG7{slash}SDA4{slash}PMA4{slash}RG7-Pad11)") (class "Default")
      (node (ref "U$3") (pin "11") (pinfunction "EBIA4/AN13/C1INC/ECRS/RPG7/SDA4/PMA4/RG7_11") (pintype "bidirectional"))
    )
    (net (code "140") (name "unconnected-(U$3-EBIA7{slash}AN49{slash}RPB9{slash}PMA7{slash}RB9-Pad33)") (class "Default")
      (node (ref "U$3") (pin "33") (pinfunction "EBIA7/AN49/RPB9/PMA7/RB9_33") (pintype "bidirectional"))
    )
    (net (code "141") (name "unconnected-(U$3-EBIOE{slash}AN19{slash}RPC4{slash}PMRD{slash}RC4-Pad9)") (class "Default")
      (node (ref "U$3") (pin "9") (pinfunction "EBIOE/AN19/RPC4/PMRD/RC4_9") (pintype "bidirectional"))
    )
    (net (code "142") (name "unconnected-(U$3-EBIWE{slash}AN20{slash}RPC3{slash}PMWR{slash}RC3-Pad8)") (class "Default")
      (node (ref "U$3") (pin "8") (pinfunction "EBIWE/AN20/RPC3/PMWR/RC3_8") (pintype "bidirectional"))
    )
    (net (code "143") (name "unconnected-(U$3-OSC2{slash}CLKO{slash}RC15-Pad50)") (class "Default")
      (node (ref "U$3") (pin "50") (pinfunction "OSC2/CLKO/RC15_50") (pintype "bidirectional"))
    )
    (net (code "144") (name "unconnected-(U$3-PGED2{slash}AN47{slash}RPB7{slash}RB7-Pad27)") (class "Default")
      (node (ref "U$3") (pin "27") (pinfunction "PGED2/AN47/RPB7/RB7_27") (pintype "bidirectional"))
    )
    (net (code "145") (name "unconnected-(U$3-TDO{slash}EBIA17{slash}AN31{slash}RPF12{slash}RF12-Pad40)") (class "Default")
      (node (ref "U$3") (pin "40") (pinfunction "TDO/EBIA17/AN31/RPF12/RF12_40") (pintype "bidirectional"))
    )
    (net (code "146") (name "unconnected-(U$3-TMS{slash}EBIA16{slash}AN24{slash}RA0-Pad17)") (class "Default")
      (node (ref "U$3") (pin "17") (pinfunction "TMS/EBIA16/AN24/RA0_17") (pintype "bidirectional"))
    )
    (net (code "147") (name "unconnected-(U$3-VREF+{slash}CVREF+{slash}AN28{slash}AERXD3{slash}RA10-Pad29)") (class "Default")
      (node (ref "U$3") (pin "29") (pinfunction "VREF+/CVREF+/AN28/AERXD3/RA10_29") (pintype "bidirectional"))
    )
    (net (code "148") (name "unconnected-(U$3-VREF-{slash}CVREF-{slash}AN27{slash}AERXD2{slash}RA9-Pad28)") (class "Default")
      (node (ref "U$3") (pin "28") (pinfunction "VREF-/CVREF-/AN27/AERXD2/RA9_28") (pintype "bidirectional"))
    )
    (net (code "149") (name "unconnected-(U$7-TRI-Pad1)") (class "Default")
      (node (ref "U$7") (pin "1") (pinfunction "TRI_1") (pintype "input"))
    )
    (net (code "150") (name "unconnected-(U1-NC-Pad1)") (class "Default")
      (node (ref "U1") (pin "1") (pinfunction "NC_1") (pintype "bidirectional"))
    )
    (net (code "151") (name "unconnected-(U1-RSV-Pad8)") (class "Default")
      (node (ref "U1") (pin "8") (pinfunction "RSV_8") (pintype "bidirectional"))
    )
    (net (code "152") (name "unconnected-(U2A-LINEIN-Pad48)") (class "Default")
      (node (ref "U2") (pin "48") (pinfunction "LINEIN_48") (pintype "bidirectional"))
    )
    (net (code "153") (name "unconnected-(U2A-MICN-Pad2)") (class "Default")
      (node (ref "U2") (pin "2") (pinfunction "MICN_2") (pintype "bidirectional"))
    )
    (net (code "154") (name "unconnected-(U2A-MICP-Pad1)") (class "Default")
      (node (ref "U2") (pin "1") (pinfunction "MICP_1") (pintype "bidirectional"))
    )
    (net (code "155") (name "unconnected-(U2A-TX-Pad27)") (class "Default")
      (node (ref "U2") (pin "27") (pinfunction "TX_27") (pintype "bidirectional"))
    )
    (net (code "156") (name "unconnected-(U2A-VCO-Pad15)") (class "Default")
      (node (ref "U2") (pin "15") (pinfunction "VCO_15") (pintype "bidirectional"))
    )
  )
)
